# STM32H7XX_100PIN.net
KiCad netlist of a schematic drawn in Altium Designer
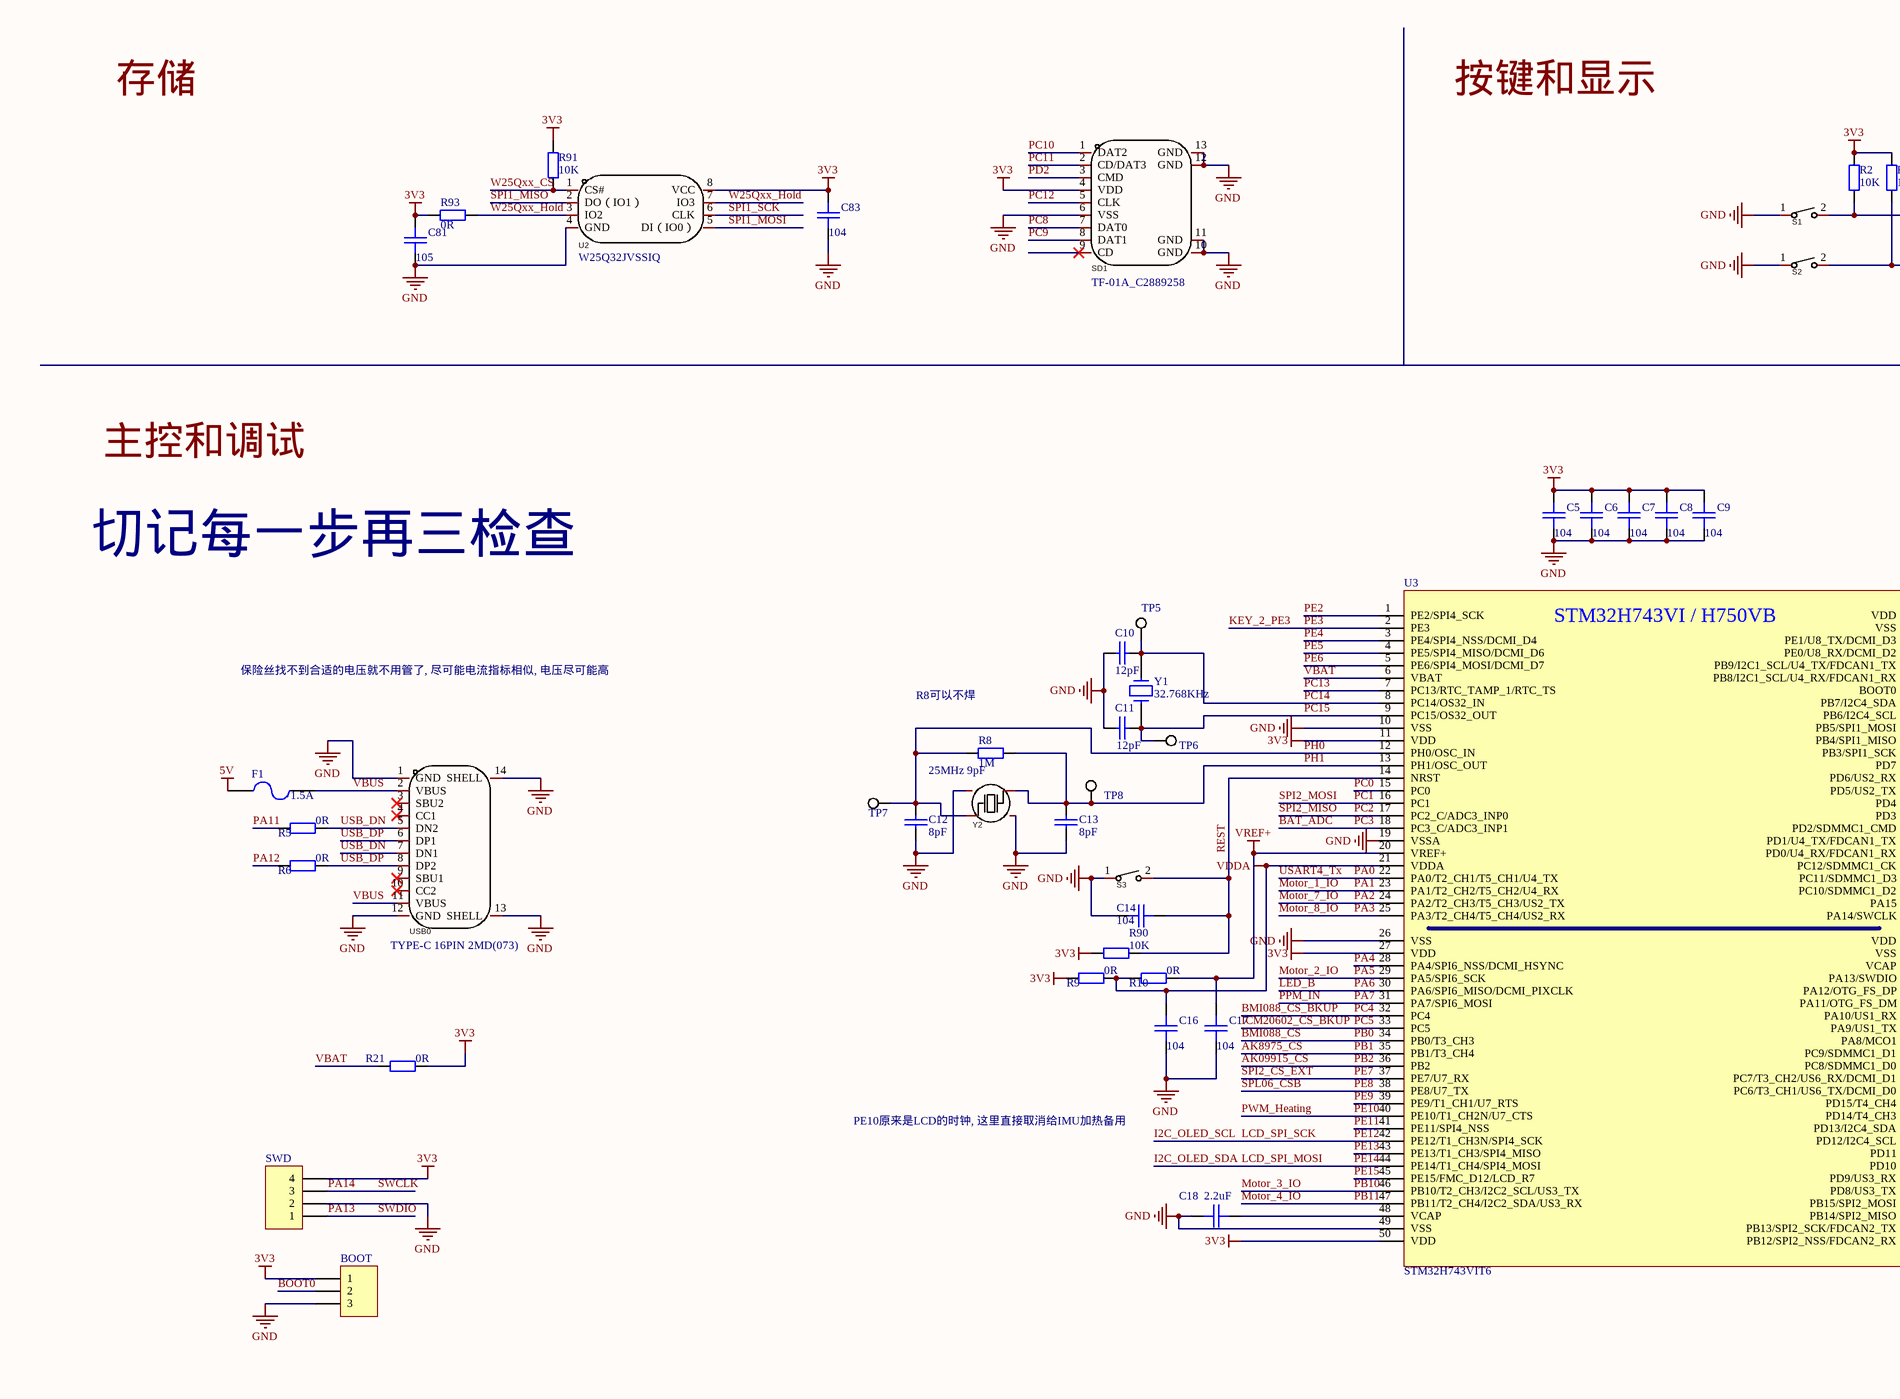
[diagram p0: STM32H7XX_100PIN.SchDoc, top left]
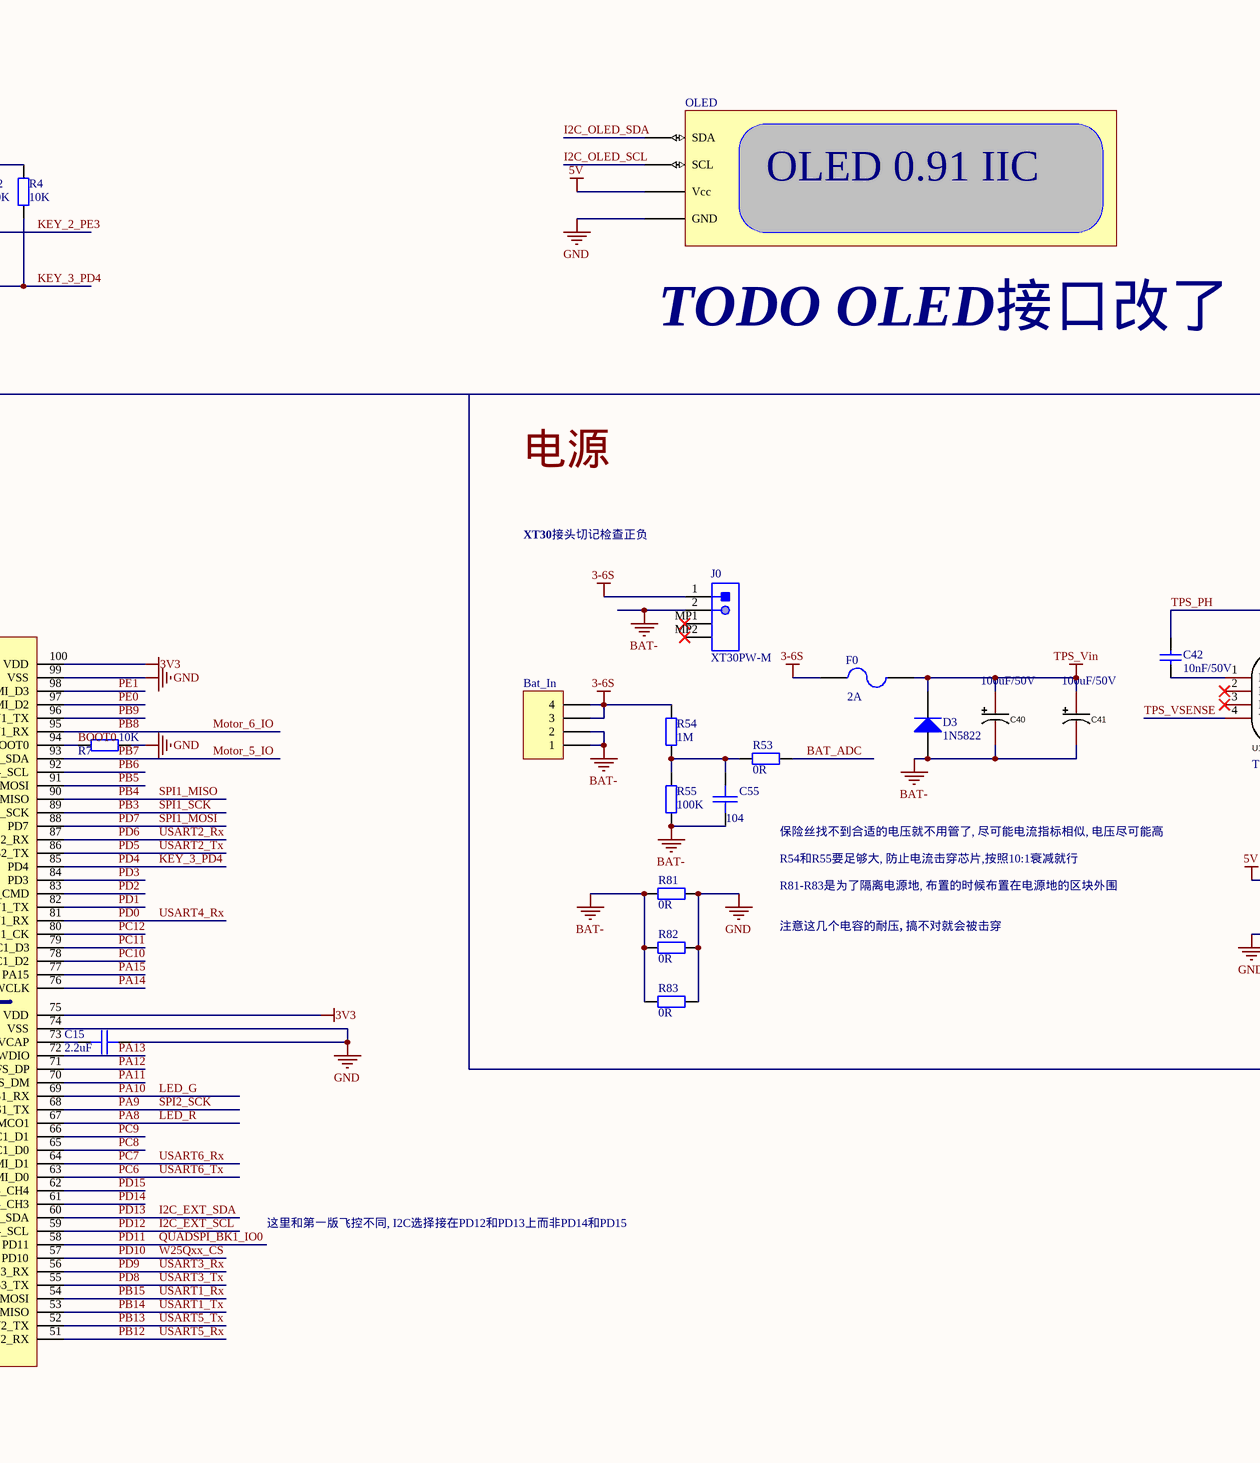
[diagram p1: STM32H7XX_100PIN.SchDoc, top middle]
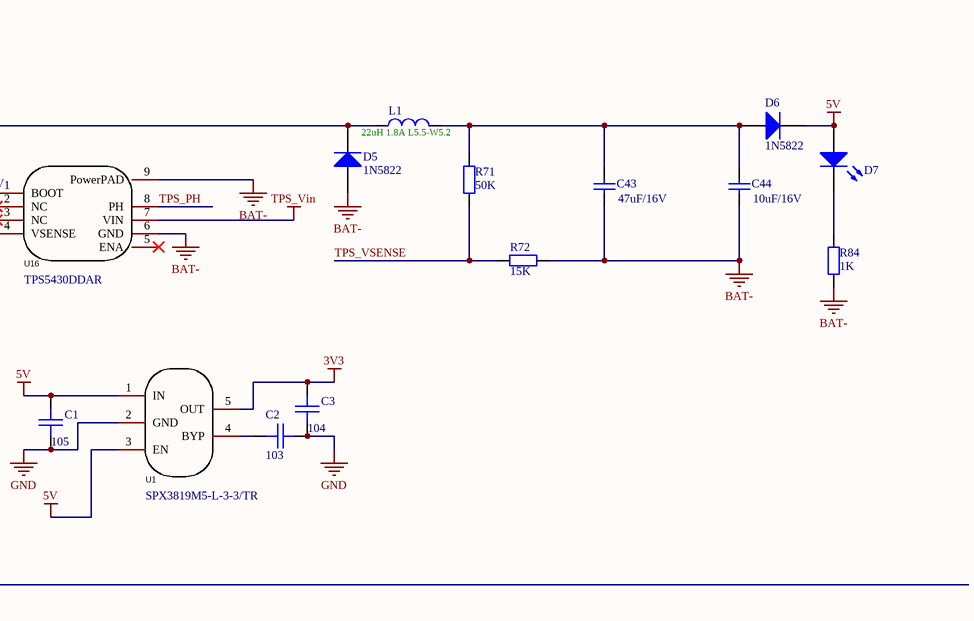
[diagram p2: STM32H7XX_100PIN.SchDoc, top right]
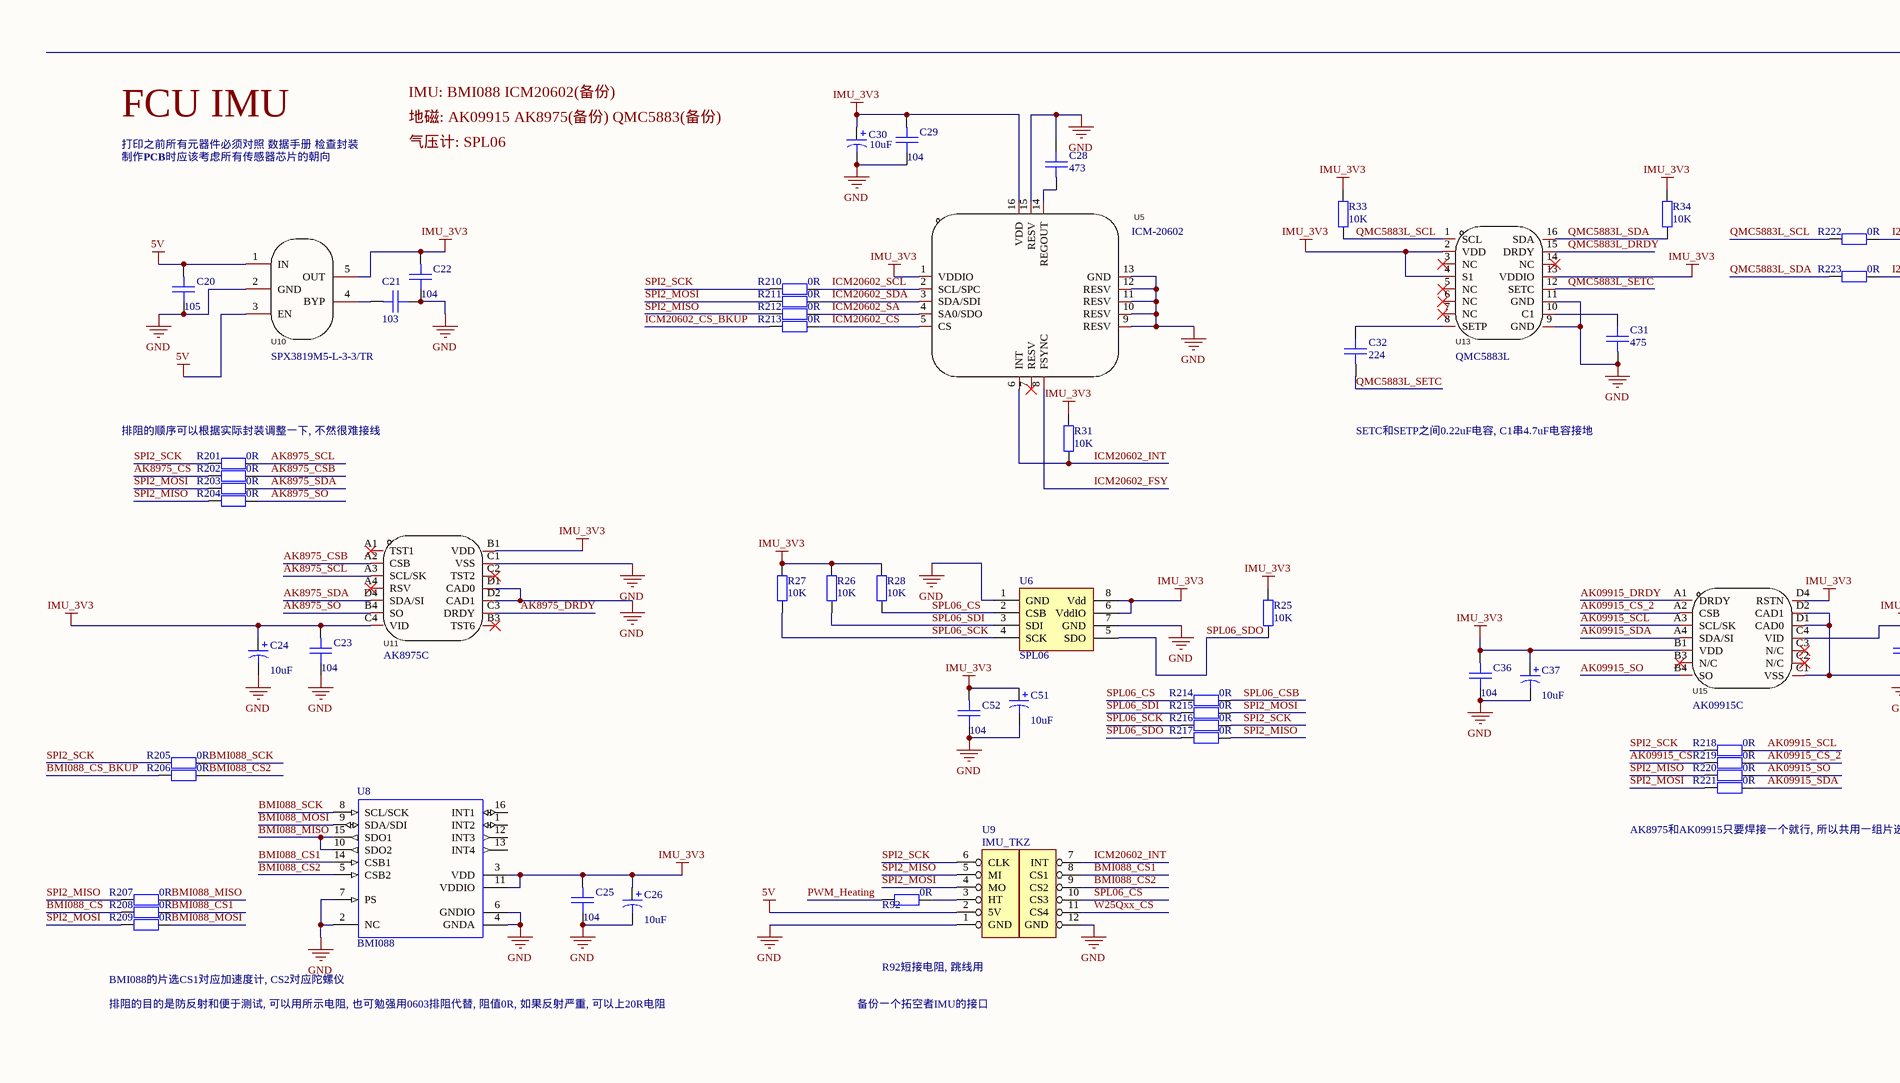
[diagram p3: STM32H7XX_100PIN.SchDoc, bottom left]
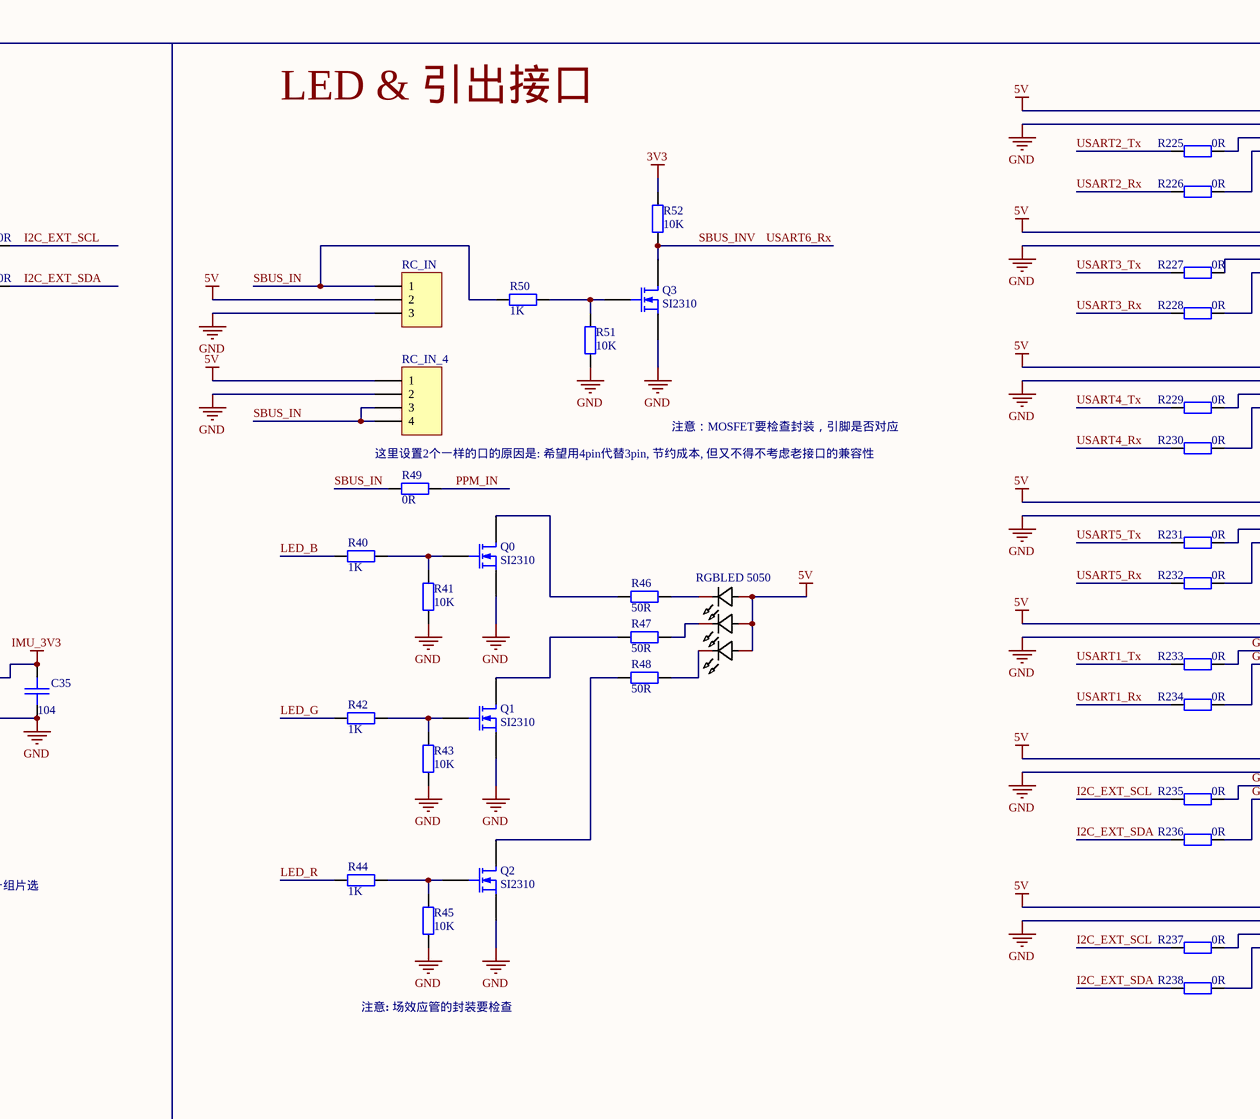
[diagram p4: STM32H7XX_100PIN.SchDoc, bottom middle]
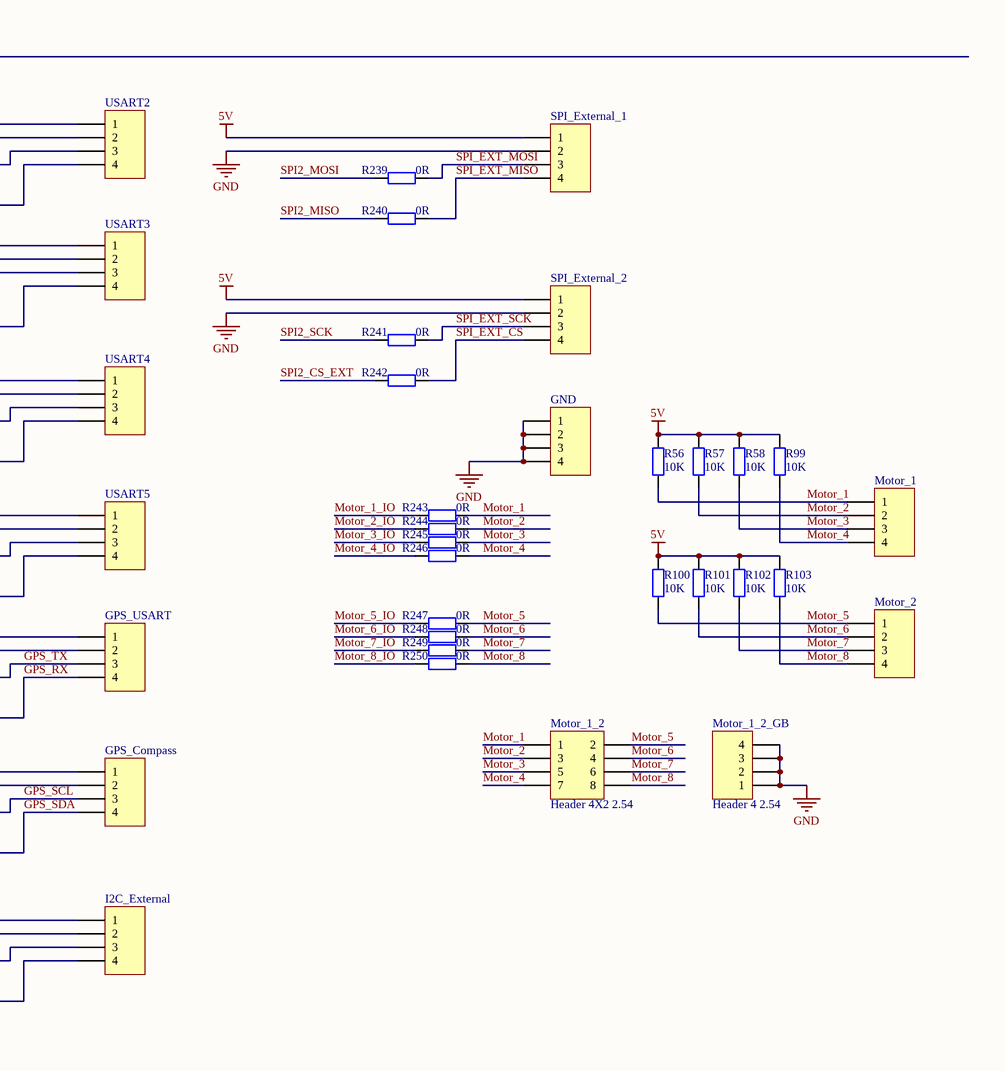
[diagram p5: STM32H7XX_100PIN.SchDoc, bottom right]

(export (version "E")
  (design (tool "Eeschema 10.0.6"))
  (components
    (comp (ref "Bat_In")
      (value "SH1.0-4")
      (footprint "飞控底板兼容版:SH_1.0_卧")
      (description "Header, 4-Pin")
      (fields (field (name "PUBLISHER") "Altium Limited"))
      (libsource (lib "") (part "Header 4_1"))
    )
    (comp (ref "BOOT")
      (value "Header 3 2.54")
      (footprint "HDR1X3")
      (description "Header, 3-Pin")
      (fields (field (name "PUBLISHER") "Altium Limited"))
      (libsource (lib "Miscellaneous Connectors") (part "Header 3"))
    )
    (comp (ref "C1") (value "105") (footprint "C0402") (libsource (lib "YT1_SCH_99SE") (part "CAP")))
    (comp (ref "C2") (value "103") (footprint "C0402") (libsource (lib "YT1_SCH_99SE") (part "CAP")))
    (comp (ref "C3") (value "104") (footprint "C0402") (libsource (lib "YT1_SCH_99SE") (part "CAP")))
    (comp (ref "C5") (value "104") (footprint "C0402") (libsource (lib "YT1_SCH_99SE") (part "CAP")))
    (comp (ref "C6") (value "104") (footprint "C0402") (libsource (lib "YT1_SCH_99SE") (part "CAP")))
    (comp (ref "C7") (value "104") (footprint "C0402") (libsource (lib "YT1_SCH_99SE") (part "CAP")))
    (comp (ref "C8") (value "104") (footprint "C0402") (libsource (lib "YT1_SCH_99SE") (part "CAP")))
    (comp (ref "C9") (value "104") (footprint "C0402") (libsource (lib "YT1_SCH_99SE") (part "CAP")))
    (comp (ref "C10")
      (value "12pF")
      (footprint "C0402")
      (description "Capcitor")
      (libsource (lib "LXKJSJ") (part "CAP"))
    )
    (comp (ref "C11")
      (value "12pF")
      (footprint "C0402")
      (description "Capcitor")
      (libsource (lib "LXKJSJ") (part "CAP"))
    )
    (comp (ref "C12")
      (value "8pF")
      (footprint "C0402")
      (description "Capcitor")
      (libsource (lib "LXKJSJ") (part "CAP"))
    )
    (comp (ref "C13")
      (value "8pF")
      (footprint "C0402")
      (description "Capcitor")
      (libsource (lib "LXKJSJ") (part "CAP"))
    )
    (comp (ref "C14") (value "104") (footprint "C0402") (libsource (lib "YT1_SCH_99SE") (part "CAP")))
    (comp (ref "C15") (value "2.2uF") (footprint "C0402") (libsource (lib "YT1_SCH_99SE") (part "CAP")))
    (comp (ref "C16") (value "104") (footprint "C0402") (libsource (lib "YT1_SCH_99SE") (part "CAP")))
    (comp (ref "C17") (value "104") (footprint "C0402") (libsource (lib "YT1_SCH_99SE") (part "CAP")))
    (comp (ref "C18") (value "2.2uF") (footprint "C0402") (libsource (lib "YT1_SCH_99SE") (part "CAP")))
    (comp (ref "C20") (value "105") (footprint "C0402") (libsource (lib "YT1_SCH_99SE") (part "CAP")))
    (comp (ref "C21") (value "103") (footprint "C0402") (libsource (lib "YT1_SCH_99SE") (part "CAP")))
    (comp (ref "C22") (value "104") (footprint "C0402") (libsource (lib "YT1_SCH_99SE") (part "CAP")))
    (comp (ref "C23") (value "104") (footprint "C0402") (libsource (lib "YT1_SCH_99SE") (part "CAP")))
    (comp (ref "C24")
      (value "10uF")
      (footprint "飞控-REV1:TAN-A(3216-18)")
      (description "Polarized Capacitor (Surface Mount)")
      (fields (field (name "PUBLISHER") "Altium Limited"))
      (libsource (lib "Miscellaneous Devices") (part "Cap Pol3"))
    )
    (comp (ref "C25") (value "104") (footprint "C0402") (libsource (lib "YT1_SCH_99SE") (part "CAP")))
    (comp (ref "C26")
      (value "10uF")
      (footprint "TAN-A(3216-18)")
      (description "Polarized Capacitor (Surface Mount)")
      (fields (field (name "PUBLISHER") "Altium Limited"))
      (libsource (lib "Miscellaneous Devices") (part "Cap Pol3"))
    )
    (comp (ref "C28") (value "473") (footprint "C0402") (libsource (lib "YT1_SCH_99SE") (part "CAP")))
    (comp (ref "C29") (value "104") (footprint "C0402") (libsource (lib "YT1_SCH_99SE") (part "CAP")))
    (comp (ref "C30")
      (value "10uF")
      (footprint "TAN-A(3216-18)")
      (description "Polarized Capacitor (Surface Mount)")
      (fields (field (name "PUBLISHER") "Altium Limited"))
      (libsource (lib "Miscellaneous Devices") (part "Cap Pol3"))
    )
    (comp (ref "C31") (value "475") (footprint "C0402") (libsource (lib "YT1_SCH_99SE") (part "CAP")))
    (comp (ref "C32") (value "224") (footprint "C0402") (libsource (lib "YT1_SCH_99SE") (part "CAP")))
    (comp (ref "C35") (value "104") (footprint "C0402") (libsource (lib "YT1_SCH_99SE") (part "CAP")))
    (comp (ref "C36") (value "104") (footprint "C0402") (libsource (lib "YT1_SCH_99SE") (part "CAP")))
    (comp (ref "C37")
      (value "10uF")
      (footprint "TAN-A(3216-18)")
      (description "Polarized Capacitor (Surface Mount)")
      (fields (field (name "PUBLISHER") "Altium Limited"))
      (libsource (lib "Miscellaneous Devices") (part "Cap Pol3"))
    )
    (comp (ref "C40")
      (value "100uF/50V")
      (footprint "CAP-SMD_BD6.3-L6.6-W6.6-FD")
      (fields
        (field (name "MANUFACTURER") "PANASONIC(����)")
        (field (name "MANUFACTURER PART") "EEEFTH101XAP")
        (field (name "TOLERANCE") "��20%")
      )
      (libsource (lib "FCU_Integrated_Library") (part "EEEFTH101XAP"))
    )
    (comp (ref "C41")
      (value "100uF/50V")
      (footprint "CAP-SMD_BD6.3-L6.6-W6.6-FD")
      (fields
        (field (name "MANUFACTURER") "PANASONIC(����)")
        (field (name "MANUFACTURER PART") "EEEFTH101XAP")
        (field (name "TOLERANCE") "��20%")
      )
      (libsource (lib "FCU_Integrated_Library") (part "EEEFTH101XAP"))
    )
    (comp (ref "C42")
      (value "10nF/50V")
      (footprint "STM32H_3D:C1206")
      (fields (field (name "TOLERANCE") "Â±10%"))
      (libsource (lib "FCU_Integrated_Library") (part "CMP-1035-02588-1"))
    )
    (comp (ref "C43")
      (value "47uF/16V")
      (footprint "STM32H_3D:C1210")
      (fields (field (name "TOLERANCE") "Â±10%"))
      (libsource (lib "FCU_Integrated_Library") (part "CMP-1035-02588-1"))
    )
    (comp (ref "C44")
      (value "10uF/16V")
      (footprint "STM32H_3D:C1210")
      (fields (field (name "TOLERANCE") "Â±10%"))
      (libsource (lib "FCU_Integrated_Library") (part "CMP-1035-02588-1"))
    )
    (comp (ref "C51")
      (value "10uF")
      (footprint "TAN-A(3216-18)")
      (description "Polarized Capacitor (Surface Mount)")
      (fields (field (name "PUBLISHER") "Altium Limited"))
      (libsource (lib "Miscellaneous Devices") (part "Cap Pol3"))
    )
    (comp (ref "C52") (value "104") (footprint "C0402") (libsource (lib "YT1_SCH_99SE") (part "CAP")))
    (comp (ref "C55") (value "104") (footprint "C0402") (libsource (lib "YT1_SCH_99SE") (part "CAP")))
    (comp (ref "C81") (value "105") (footprint "C0402") (libsource (lib "YT1_SCH_99SE") (part "CAP")))
    (comp (ref "C83") (value "104") (footprint "C0402") (libsource (lib "YT1_SCH_99SE") (part "CAP")))
    (comp (ref "D0")
      (value "RGBLED 5050")
      (footprint "LED-SMD_6P-L5.0-W5.0-TL_TC5050RGBF08")
      (fields
        (field (name "MANUFACTURER") "TCWIN(���)")
        (field (name "MANUFACTURER PART") "TC5050RGBF08-3CJH-AF53A")
      )
      (libsource (lib "FCU_Integrated_Library") (part "TC5050RGBF08-3CJH-AF53A"))
    )
    (comp (ref "D3")
      (value "1N5822")
      (footprint "FCU_Integrated_Library:SMA_L4.3-W2.5-LS5.0-RD")
      (description "SS34 Diode")
      (fields (field (name "PUBLISHER") "mazhongwei"))
      (libsource (lib "FCU_Integrated_Library") (part "SS34 Diode"))
    )
    (comp (ref "D5")
      (value "1N5822")
      (footprint "FCU_Integrated_Library:SMA_L4.3-W2.5-LS5.0-RD")
      (description "SS34 Diode")
      (fields (field (name "PUBLISHER") "mazhongwei"))
      (libsource (lib "FCU_Integrated_Library") (part "SS34 Diode"))
    )
    (comp (ref "D6")
      (value "1N5822")
      (footprint "FCU_Integrated_Library:SMA_L4.3-W2.5-LS5.0-RD")
      (description "SS34 Diode")
      (fields (field (name "PUBLISHER") "mazhongwei"))
      (libsource (lib "FCU_Integrated_Library") (part "SS34 Diode"))
    )
    (comp (ref "D7")
      (value "Red LED")
      (footprint "LED0603")
      (description "发光二极管")
      (fields (field (name "PUBLISHER") "Altium Limited"))
      (libsource (lib "主集成库") (part "LED0"))
    )
    (comp (ref "F0")
      (value "2A")
      (footprint "FU 1210")
      (description "保险丝")
      (fields (field (name "PUBLISHER") "Altium Limited"))
      (libsource (lib "fszhang") (part "Fuse 2"))
    )
    (comp (ref "F1")
      (value "1.5A")
      (footprint "FU 0402")
      (description "保险丝")
      (fields (field (name "PUBLISHER") "Altium Limited"))
      (libsource (lib "fszhang") (part "Fuse 2"))
    )
    (comp (ref "GND")
      (value "SH1.0-4")
      (footprint "飞控底板兼容版:SH_1.0_卧")
      (description "Header, 4-Pin")
      (fields (field (name "PUBLISHER") "Altium Limited"))
      (libsource (lib "Miscellaneous Connectors") (part "Header 4"))
    )
    (comp (ref "GPS_Compass")
      (value "SH1.0-4")
      (footprint "飞控底板兼容版:SH_1.0_卧")
      (description "Header, 4-Pin")
      (fields (field (name "PUBLISHER") "Altium Limited"))
      (libsource (lib "Miscellaneous Connectors") (part "Header 4"))
    )
    (comp (ref "GPS_USART")
      (value "SH1.0-4")
      (footprint "飞控底板兼容版:SH_1.0_卧")
      (description "Header, 4-Pin")
      (fields (field (name "PUBLISHER") "Altium Limited"))
      (libsource (lib "Miscellaneous Connectors") (part "Header 4"))
    )
    (comp (ref "I2C_External")
      (value "SH1.0-4")
      (footprint "飞控底板兼容版:SH_1.0_卧")
      (description "Header, 4-Pin")
      (fields (field (name "PUBLISHER") "Altium Limited"))
      (libsource (lib "Miscellaneous Connectors") (part "Header 4"))
    )
    (comp (ref "J0")
      (value "XT30PW-M")
      (footprint "AMASS-XT30PW-M")
      (description "XT Series Lithium Battery Male Connector, 4-pin TH")
      (fields (field (name "MANUFACTURER") "AMASS") (field (name "PUBLISHER") "Bolgen Studio"))
      (libsource (lib "Changzhou Amass Lithium Battery Connector") (part "XT30PW-M"))
    )
    (comp (ref "L1")
      (value "22uH 1.8A L5.5-W5.2")
      (footprint "FCU_Integrated_Library:IND-SMD_L5.5-W5.2")
      (libsource (lib "FCU_Integrated_Library") (part "INDUCTOR_2"))
    )
    (comp (ref "Motor_1")
      (value "SH1.0-4")
      (footprint "飞控底板兼容版:SH_1.0_卧")
      (description "Header, 4-Pin")
      (fields (field (name "PUBLISHER") "Altium Limited"))
      (libsource (lib "Miscellaneous Connectors") (part "Header 4"))
    )
    (comp (ref "Motor_1_2")
      (value "Header 4X2 2.54")
      (footprint "HDR2X4")
      (description "Header, 4-Pin, Dual row")
      (fields (field (name "PUBLISHER") "Altium Limited"))
      (libsource (lib "Miscellaneous Connectors") (part "Header 4X2"))
    )
    (comp (ref "Motor_1_2_GB")
      (value "Header 4 2.54")
      (footprint "Miscellaneous Connectors:HDR1X4")
      (description "Header, 4-Pin, Right Angle")
      (fields (field (name "PUBLISHER") "Altium Limited"))
      (libsource (lib "Miscellaneous Connectors") (part "Header 4H"))
    )
    (comp (ref "Motor_2")
      (value "SH1.0-4")
      (footprint "飞控底板兼容版:SH_1.0_卧")
      (description "Header, 4-Pin")
      (fields (field (name "PUBLISHER") "Altium Limited"))
      (libsource (lib "Miscellaneous Connectors") (part "Header 4"))
    )
    (comp (ref "OLED")
      (value "OLED 0.91")
      (footprint "PCBComponent_1")
      (libsource (lib "FCU_Integrated_Library") (part "OLED 0.91"))
    )
    (comp (ref "Q0")
      (value "SI2310")
      (footprint "Explorer STM32F407封装库:SOT-23R")
      (description "N-Channel MOSFET")
      (fields (field (name "PUBLISHER") "Altium Limited"))
      (libsource (lib "Miscellaneous Devices") (part "MOSFET-N"))
    )
    (comp (ref "Q1")
      (value "SI2310")
      (footprint "Explorer STM32F407封装库:SOT-23R")
      (description "N-Channel MOSFET")
      (fields (field (name "PUBLISHER") "Altium Limited"))
      (libsource (lib "Miscellaneous Devices") (part "MOSFET-N"))
    )
    (comp (ref "Q2")
      (value "SI2310")
      (footprint "Explorer STM32F407封装库:SOT-23R")
      (description "N-Channel MOSFET")
      (fields (field (name "PUBLISHER") "Altium Limited"))
      (libsource (lib "Miscellaneous Devices") (part "MOSFET-N"))
    )
    (comp (ref "Q3")
      (value "SI2310")
      (footprint "Explorer STM32F407封装库:SOT-23R")
      (description "N-Channel MOSFET")
      (fields (field (name "PUBLISHER") "Altium Limited"))
      (libsource (lib "Miscellaneous Devices") (part "MOSFET-N"))
    )
    (comp (ref "R2")
      (value "10K")
      (footprint "R0402")
      (description "贴片电阻")
      (fields (field (name "PUBLISHER") "Altium Limited"))
      (libsource (lib "") (part "Res1_1"))
    )
    (comp (ref "R4")
      (value "10K")
      (footprint "R0402")
      (description "贴片电阻")
      (fields (field (name "PUBLISHER") "Altium Limited"))
      (libsource (lib "") (part "Res1_1"))
    )
    (comp (ref "R5")
      (value "0R")
      (footprint "STM32H_3D:R0402")
      (description "贴片电阻")
      (fields (field (name "PUBLISHER") "Altium Limited"))
      (libsource (lib "主集成库") (part "Res1"))
    )
    (comp (ref "R6")
      (value "0R")
      (footprint "R0402")
      (description "贴片电阻")
      (fields (field (name "PUBLISHER") "Altium Limited"))
      (libsource (lib "主集成库") (part "Res1"))
    )
    (comp (ref "R7")
      (value "10K")
      (footprint "R0402")
      (description "贴片电阻")
      (fields (field (name "PUBLISHER") "Altium Limited"))
      (libsource (lib "主集成库") (part "Res1"))
    )
    (comp (ref "R8")
      (value "1M")
      (footprint "R0402")
      (description "贴片电阻")
      (fields (field (name "PUBLISHER") "Altium Limited"))
      (libsource (lib "") (part "Res1_3"))
    )
    (comp (ref "R9")
      (value "0R")
      (footprint "R0402")
      (description "贴片电阻")
      (fields (field (name "PUBLISHER") "Altium Limited"))
      (libsource (lib "主集成库") (part "Res1"))
    )
    (comp (ref "R10")
      (value "0R")
      (footprint "R0402")
      (description "贴片电阻")
      (fields (field (name "PUBLISHER") "Altium Limited"))
      (libsource (lib "主集成库") (part "Res1"))
    )
    (comp (ref "R21")
      (value "0R")
      (footprint "R0402")
      (description "贴片电阻")
      (fields (field (name "PUBLISHER") "Altium Limited"))
      (libsource (lib "主集成库") (part "Res1"))
    )
    (comp (ref "R25")
      (value "10K")
      (footprint "R0402")
      (description "贴片电阻")
      (fields (field (name "PUBLISHER") "Altium Limited"))
      (libsource (lib "") (part "Res1_1"))
    )
    (comp (ref "R26")
      (value "10K")
      (footprint "R0402")
      (description "贴片电阻")
      (fields (field (name "PUBLISHER") "Altium Limited"))
      (libsource (lib "") (part "Res1_1"))
    )
    (comp (ref "R27")
      (value "10K")
      (footprint "R0402")
      (description "贴片电阻")
      (fields (field (name "PUBLISHER") "Altium Limited"))
      (libsource (lib "") (part "Res1_1"))
    )
    (comp (ref "R28")
      (value "10K")
      (footprint "R0402")
      (description "贴片电阻")
      (fields (field (name "PUBLISHER") "Altium Limited"))
      (libsource (lib "") (part "Res1_1"))
    )
    (comp (ref "R31")
      (value "10K")
      (footprint "R0402")
      (description "贴片电阻")
      (fields (field (name "PUBLISHER") "Altium Limited"))
      (libsource (lib "") (part "Res1_1"))
    )
    (comp (ref "R33")
      (value "10K")
      (footprint "R0402")
      (description "贴片电阻")
      (fields (field (name "PUBLISHER") "Altium Limited"))
      (libsource (lib "") (part "Res1_1"))
    )
    (comp (ref "R34")
      (value "10K")
      (footprint "R0402")
      (description "贴片电阻")
      (fields (field (name "PUBLISHER") "Altium Limited"))
      (libsource (lib "") (part "Res1_1"))
    )
    (comp (ref "R40")
      (value "1K")
      (footprint "R0402")
      (description "贴片电阻")
      (fields (field (name "PUBLISHER") "Altium Limited"))
      (libsource (lib "") (part "Res1_2"))
    )
    (comp (ref "R41")
      (value "10K")
      (footprint "R0402")
      (description "贴片电阻")
      (fields (field (name "PUBLISHER") "Altium Limited"))
      (libsource (lib "fszhang") (part "Res1"))
    )
    (comp (ref "R42")
      (value "1K")
      (footprint "R0402")
      (description "贴片电阻")
      (fields (field (name "PUBLISHER") "Altium Limited"))
      (libsource (lib "") (part "Res1_2"))
    )
    (comp (ref "R43")
      (value "10K")
      (footprint "R0402")
      (description "贴片电阻")
      (fields (field (name "PUBLISHER") "Altium Limited"))
      (libsource (lib "fszhang") (part "Res1"))
    )
    (comp (ref "R44")
      (value "1K")
      (footprint "R0402")
      (description "贴片电阻")
      (fields (field (name "PUBLISHER") "Altium Limited"))
      (libsource (lib "") (part "Res1_2"))
    )
    (comp (ref "R45")
      (value "10K")
      (footprint "R0402")
      (description "贴片电阻")
      (fields (field (name "PUBLISHER") "Altium Limited"))
      (libsource (lib "fszhang") (part "Res1"))
    )
    (comp (ref "R46")
      (value "50R")
      (footprint "R0402")
      (description "贴片电阻")
      (fields (field (name "PUBLISHER") "Altium Limited"))
      (libsource (lib "") (part "10K_1"))
    )
    (comp (ref "R47")
      (value "50R")
      (footprint "R0402")
      (description "贴片电阻")
      (fields (field (name "PUBLISHER") "Altium Limited"))
      (libsource (lib "") (part "10K_1"))
    )
    (comp (ref "R48")
      (value "50R")
      (footprint "R0402")
      (description "贴片电阻")
      (fields (field (name "PUBLISHER") "Altium Limited"))
      (libsource (lib "") (part "10K_1"))
    )
    (comp (ref "R49")
      (value "0R")
      (footprint "R0402")
      (description "贴片电阻")
      (fields (field (name "PUBLISHER") "Altium Limited"))
      (libsource (lib "") (part "Res1_2"))
    )
    (comp (ref "R50")
      (value "1K")
      (footprint "R0402")
      (description "贴片电阻")
      (fields (field (name "PUBLISHER") "Altium Limited"))
      (libsource (lib "") (part "Res1_2"))
    )
    (comp (ref "R51")
      (value "10K")
      (footprint "R0402")
      (description "贴片电阻")
      (fields (field (name "PUBLISHER") "Altium Limited"))
      (libsource (lib "fszhang") (part "Res1"))
    )
    (comp (ref "R52")
      (value "10K")
      (footprint "R0402")
      (description "贴片电阻")
      (fields (field (name "PUBLISHER") "Altium Limited"))
      (libsource (lib "fszhang") (part "Res1"))
    )
    (comp (ref "R53")
      (value "0R")
      (footprint "R0402")
      (description "贴片电阻")
      (fields (field (name "PUBLISHER") "Altium Limited"))
      (libsource (lib "") (part "Res1_2"))
    )
    (comp (ref "R54")
      (value "1M")
      (footprint "R0402")
      (description "贴片电阻")
      (fields (field (name "PUBLISHER") "Altium Limited"))
      (libsource (lib "fszhang") (part "Res1"))
    )
    (comp (ref "R55")
      (value "100K")
      (footprint "R0402")
      (description "贴片电阻")
      (fields (field (name "PUBLISHER") "Altium Limited"))
      (libsource (lib "fszhang") (part "Res1"))
    )
    (comp (ref "R56")
      (value "10K")
      (footprint "R0402")
      (description "贴片电阻")
      (fields (field (name "PUBLISHER") "Altium Limited"))
      (libsource (lib "fszhang") (part "10K"))
    )
    (comp (ref "R57")
      (value "10K")
      (footprint "R0402")
      (description "贴片电阻")
      (fields (field (name "PUBLISHER") "Altium Limited"))
      (libsource (lib "fszhang") (part "10K"))
    )
    (comp (ref "R58")
      (value "10K")
      (footprint "R0402")
      (description "贴片电阻")
      (fields (field (name "PUBLISHER") "Altium Limited"))
      (libsource (lib "fszhang") (part "10K"))
    )
    (comp (ref "R71")
      (value "50K")
      (footprint "0805")
      (description "贴片电阻")
      (fields (field (name "PUBLISHER") "Altium Limited"))
      (libsource (lib "fszhang") (part "Res1"))
    )
    (comp (ref "R72")
      (value "15K")
      (footprint "0805")
      (description "贴片电阻")
      (fields (field (name "PUBLISHER") "Altium Limited"))
      (libsource (lib "") (part "Res1_3"))
    )
    (comp (ref "R81")
      (value "0R")
      (footprint "R0402")
      (description "贴片电阻")
      (fields (field (name "PUBLISHER") "Altium Limited"))
      (libsource (lib "") (part "Res1_2"))
    )
    (comp (ref "R82")
      (value "0R")
      (footprint "R0402")
      (description "贴片电阻")
      (fields (field (name "PUBLISHER") "Altium Limited"))
      (libsource (lib "") (part "Res1_2"))
    )
    (comp (ref "R83")
      (value "0R")
      (footprint "R0402")
      (description "贴片电阻")
      (fields (field (name "PUBLISHER") "Altium Limited"))
      (libsource (lib "") (part "Res1_2"))
    )
    (comp (ref "R84")
      (value "1K")
      (footprint "R0402")
      (description "贴片电阻")
      (fields (field (name "PUBLISHER") "Altium Limited"))
      (libsource (lib "fszhang") (part "Res1"))
    )
    (comp (ref "R90")
      (value "10K")
      (footprint "R0402")
      (description "贴片电阻")
      (fields (field (name "PUBLISHER") "Altium Limited"))
      (libsource (lib "主集成库") (part "Res1"))
    )
    (comp (ref "R91")
      (value "10K")
      (footprint "R0402")
      (description "贴片电阻")
      (fields (field (name "PUBLISHER") "Altium Limited"))
      (libsource (lib "") (part "Res1_1"))
    )
    (comp (ref "R92")
      (value "0R")
      (footprint "R0402")
      (description "贴片电阻")
      (fields (field (name "PUBLISHER") "Altium Limited"))
      (libsource (lib "主集成库") (part "Res1"))
    )
    (comp (ref "R93")
      (value "0R")
      (footprint "R0402")
      (description "贴片电阻")
      (fields (field (name "Comment") "10K") (field (name "PUBLISHER") "Altium Limited"))
      (libsource (lib "") (part "Res1_2"))
    )
    (comp (ref "R99")
      (value "10K")
      (footprint "R0402")
      (description "贴片电阻")
      (fields (field (name "PUBLISHER") "Altium Limited"))
      (libsource (lib "fszhang") (part "10K"))
    )
    (comp (ref "R100")
      (value "10K")
      (footprint "R0402")
      (description "贴片电阻")
      (fields (field (name "PUBLISHER") "Altium Limited"))
      (libsource (lib "fszhang") (part "10K"))
    )
    (comp (ref "R101")
      (value "10K")
      (footprint "R0402")
      (description "贴片电阻")
      (fields (field (name "PUBLISHER") "Altium Limited"))
      (libsource (lib "fszhang") (part "10K"))
    )
    (comp (ref "R102")
      (value "10K")
      (footprint "R0402")
      (description "贴片电阻")
      (fields (field (name "PUBLISHER") "Altium Limited"))
      (libsource (lib "fszhang") (part "10K"))
    )
    (comp (ref "R103")
      (value "10K")
      (footprint "R0402")
      (description "贴片电阻")
      (fields (field (name "PUBLISHER") "Altium Limited"))
      (libsource (lib "fszhang") (part "10K"))
    )
    (comp (ref "R201")
      (value "0R")
      (footprint "R0402")
      (description "贴片电阻")
      (fields (field (name "PUBLISHER") "Altium Limited"))
      (libsource (lib "主集成库") (part "Res1"))
    )
    (comp (ref "R202")
      (value "0R")
      (footprint "R0402")
      (description "贴片电阻")
      (fields (field (name "PUBLISHER") "Altium Limited"))
      (libsource (lib "主集成库") (part "Res1"))
    )
    (comp (ref "R203")
      (value "0R")
      (footprint "R0402")
      (description "贴片电阻")
      (fields (field (name "PUBLISHER") "Altium Limited"))
      (libsource (lib "主集成库") (part "Res1"))
    )
    (comp (ref "R204")
      (value "0R")
      (footprint "R0402")
      (description "贴片电阻")
      (fields (field (name "PUBLISHER") "Altium Limited"))
      (libsource (lib "主集成库") (part "Res1"))
    )
    (comp (ref "R205")
      (value "0R")
      (footprint "R0402")
      (description "贴片电阻")
      (fields (field (name "PUBLISHER") "Altium Limited"))
      (libsource (lib "主集成库") (part "Res1"))
    )
    (comp (ref "R206")
      (value "0R")
      (footprint "R0402")
      (description "贴片电阻")
      (fields (field (name "PUBLISHER") "Altium Limited"))
      (libsource (lib "主集成库") (part "Res1"))
    )
    (comp (ref "R207")
      (value "0R")
      (footprint "R0402")
      (description "贴片电阻")
      (fields (field (name "PUBLISHER") "Altium Limited"))
      (libsource (lib "主集成库") (part "Res1"))
    )
    (comp (ref "R208")
      (value "0R")
      (footprint "R0402")
      (description "贴片电阻")
      (fields (field (name "PUBLISHER") "Altium Limited"))
      (libsource (lib "主集成库") (part "Res1"))
    )
    (comp (ref "R209")
      (value "0R")
      (footprint "R0402")
      (description "贴片电阻")
      (fields (field (name "PUBLISHER") "Altium Limited"))
      (libsource (lib "主集成库") (part "Res1"))
    )
    (comp (ref "R210")
      (value "0R")
      (footprint "R0402")
      (description "贴片电阻")
      (fields (field (name "PUBLISHER") "Altium Limited"))
      (libsource (lib "主集成库") (part "Res1"))
    )
    (comp (ref "R211")
      (value "0R")
      (footprint "R0402")
      (description "贴片电阻")
      (fields (field (name "PUBLISHER") "Altium Limited"))
      (libsource (lib "主集成库") (part "Res1"))
    )
    (comp (ref "R212")
      (value "0R")
      (footprint "R0402")
      (description "贴片电阻")
      (fields (field (name "PUBLISHER") "Altium Limited"))
      (libsource (lib "主集成库") (part "Res1"))
    )
    (comp (ref "R213")
      (value "0R")
      (footprint "R0402")
      (description "贴片电阻")
      (fields (field (name "PUBLISHER") "Altium Limited"))
      (libsource (lib "主集成库") (part "Res1"))
    )
    (comp (ref "R214")
      (value "0R")
      (footprint "R0402")
      (description "贴片电阻")
      (fields (field (name "PUBLISHER") "Altium Limited"))
      (libsource (lib "主集成库") (part "Res1"))
    )
    (comp (ref "R215")
      (value "0R")
      (footprint "R0402")
      (description "贴片电阻")
      (fields (field (name "PUBLISHER") "Altium Limited"))
      (libsource (lib "主集成库") (part "Res1"))
    )
    (comp (ref "R216")
      (value "0R")
      (footprint "R0402")
      (description "贴片电阻")
      (fields (field (name "PUBLISHER") "Altium Limited"))
      (libsource (lib "主集成库") (part "Res1"))
    )
    (comp (ref "R217")
      (value "0R")
      (footprint "R0402")
      (description "贴片电阻")
      (fields (field (name "PUBLISHER") "Altium Limited"))
      (libsource (lib "主集成库") (part "Res1"))
    )
    (comp (ref "R218")
      (value "0R")
      (footprint "R0402")
      (description "贴片电阻")
      (fields (field (name "PUBLISHER") "Altium Limited"))
      (libsource (lib "主集成库") (part "Res1"))
    )
    (comp (ref "R219")
      (value "0R")
      (footprint "R0402")
      (description "贴片电阻")
      (fields (field (name "PUBLISHER") "Altium Limited"))
      (libsource (lib "主集成库") (part "Res1"))
    )
    (comp (ref "R220")
      (value "0R")
      (footprint "R0402")
      (description "贴片电阻")
      (fields (field (name "PUBLISHER") "Altium Limited"))
      (libsource (lib "主集成库") (part "Res1"))
    )
    (comp (ref "R221")
      (value "0R")
      (footprint "R0402")
      (description "贴片电阻")
      (fields (field (name "PUBLISHER") "Altium Limited"))
      (libsource (lib "主集成库") (part "Res1"))
    )
    (comp (ref "R222")
      (value "0R")
      (footprint "R0402")
      (description "贴片电阻")
      (fields (field (name "PUBLISHER") "Altium Limited"))
      (libsource (lib "主集成库") (part "Res1"))
    )
    (comp (ref "R223")
      (value "0R")
      (footprint "R0402")
      (description "贴片电阻")
      (fields (field (name "PUBLISHER") "Altium Limited"))
      (libsource (lib "主集成库") (part "Res1"))
    )
    (comp (ref "R225")
      (value "0R")
      (footprint "R0402")
      (description "贴片电阻")
      (fields (field (name "PUBLISHER") "Altium Limited"))
      (libsource (lib "主集成库") (part "Res1"))
    )
    (comp (ref "R226")
      (value "0R")
      (footprint "R0402")
      (description "贴片电阻")
      (fields (field (name "PUBLISHER") "Altium Limited"))
      (libsource (lib "主集成库") (part "Res1"))
    )
    (comp (ref "R227")
      (value "0R")
      (footprint "R0402")
      (description "贴片电阻")
      (fields (field (name "PUBLISHER") "Altium Limited"))
      (libsource (lib "主集成库") (part "Res1"))
    )
    (comp (ref "R228")
      (value "0R")
      (footprint "R0402")
      (description "贴片电阻")
      (fields (field (name "PUBLISHER") "Altium Limited"))
      (libsource (lib "主集成库") (part "Res1"))
    )
    (comp (ref "R229")
      (value "0R")
      (footprint "R0402")
      (description "贴片电阻")
      (fields (field (name "PUBLISHER") "Altium Limited"))
      (libsource (lib "主集成库") (part "Res1"))
    )
    (comp (ref "R230")
      (value "0R")
      (footprint "R0402")
      (description "贴片电阻")
      (fields (field (name "PUBLISHER") "Altium Limited"))
      (libsource (lib "主集成库") (part "Res1"))
    )
    (comp (ref "R231")
      (value "0R")
      (footprint "R0402")
      (description "贴片电阻")
      (fields (field (name "PUBLISHER") "Altium Limited"))
      (libsource (lib "主集成库") (part "Res1"))
    )
    (comp (ref "R232")
      (value "0R")
      (footprint "R0402")
      (description "贴片电阻")
      (fields (field (name "PUBLISHER") "Altium Limited"))
      (libsource (lib "主集成库") (part "Res1"))
    )
    (comp (ref "R233")
      (value "0R")
      (footprint "R0402")
      (description "贴片电阻")
      (fields (field (name "PUBLISHER") "Altium Limited"))
      (libsource (lib "主集成库") (part "Res1"))
    )
    (comp (ref "R234")
      (value "0R")
      (footprint "R0402")
      (description "贴片电阻")
      (fields (field (name "PUBLISHER") "Altium Limited"))
      (libsource (lib "主集成库") (part "Res1"))
    )
    (comp (ref "R235")
      (value "0R")
      (footprint "R0402")
      (description "贴片电阻")
      (fields (field (name "PUBLISHER") "Altium Limited"))
      (libsource (lib "主集成库") (part "Res1"))
    )
    (comp (ref "R236")
      (value "0R")
      (footprint "R0402")
      (description "贴片电阻")
      (fields (field (name "PUBLISHER") "Altium Limited"))
      (libsource (lib "主集成库") (part "Res1"))
    )
    (comp (ref "R237")
      (value "0R")
      (footprint "R0402")
      (description "贴片电阻")
      (fields (field (name "PUBLISHER") "Altium Limited"))
      (libsource (lib "主集成库") (part "Res1"))
    )
    (comp (ref "R238")
      (value "0R")
      (footprint "R0402")
      (description "贴片电阻")
      (fields (field (name "PUBLISHER") "Altium Limited"))
      (libsource (lib "主集成库") (part "Res1"))
    )
    (comp (ref "R239")
      (value "0R")
      (footprint "R0402")
      (description "贴片电阻")
      (fields (field (name "PUBLISHER") "Altium Limited"))
      (libsource (lib "主集成库") (part "Res1"))
    )
    (comp (ref "R240")
      (value "0R")
      (footprint "R0402")
      (description "贴片电阻")
      (fields (field (name "PUBLISHER") "Altium Limited"))
      (libsource (lib "主集成库") (part "Res1"))
    )
    (comp (ref "R241")
      (value "0R")
      (footprint "R0402")
      (description "贴片电阻")
      (fields (field (name "PUBLISHER") "Altium Limited"))
      (libsource (lib "主集成库") (part "Res1"))
    )
    (comp (ref "R242")
      (value "0R")
      (footprint "R0402")
      (description "贴片电阻")
      (fields (field (name "PUBLISHER") "Altium Limited"))
      (libsource (lib "主集成库") (part "Res1"))
    )
    (comp (ref "R243")
      (value "0R")
      (footprint "R0402")
      (description "贴片电阻")
      (fields (field (name "PUBLISHER") "Altium Limited"))
      (libsource (lib "主集成库") (part "Res1"))
    )
    (comp (ref "R244")
      (value "0R")
      (footprint "R0402")
      (description "贴片电阻")
      (fields (field (name "PUBLISHER") "Altium Limited"))
      (libsource (lib "主集成库") (part "Res1"))
    )
    (comp (ref "R245")
      (value "0R")
      (footprint "R0402")
      (description "贴片电阻")
      (fields (field (name "PUBLISHER") "Altium Limited"))
      (libsource (lib "主集成库") (part "Res1"))
    )
    (comp (ref "R246")
      (value "0R")
      (footprint "R0402")
      (description "贴片电阻")
      (fields (field (name "PUBLISHER") "Altium Limited"))
      (libsource (lib "主集成库") (part "Res1"))
    )
    (comp (ref "R247")
      (value "0R")
      (footprint "R0402")
      (description "贴片电阻")
      (fields (field (name "PUBLISHER") "Altium Limited"))
      (libsource (lib "主集成库") (part "Res1"))
    )
    (comp (ref "R248")
      (value "0R")
      (footprint "R0402")
      (description "贴片电阻")
      (fields (field (name "PUBLISHER") "Altium Limited"))
      (libsource (lib "主集成库") (part "Res1"))
    )
    (comp (ref "R249")
      (value "0R")
      (footprint "R0402")
      (description "贴片电阻")
      (fields (field (name "PUBLISHER") "Altium Limited"))
      (libsource (lib "主集成库") (part "Res1"))
    )
    (comp (ref "R250")
      (value "0R")
      (footprint "R0402")
      (description "贴片电阻")
      (fields (field (name "PUBLISHER") "Altium Limited"))
      (libsource (lib "主集成库") (part "Res1"))
    )
    (comp (ref "RC_IN")
      (value "SH 1.0-3")
      (footprint "飞控底板兼容版:SH_1.0_3P卧")
      (description "Header, 3-Pin")
      (fields (field (name "PUBLISHER") "Altium Limited"))
      (libsource (lib "Miscellaneous Connectors") (part "Header 3"))
    )
    (comp (ref "RC_IN_4")
      (value "SH1.0-4")
      (footprint "飞控底板兼容版:SH_1.0_卧")
      (description "Header, 4-Pin")
      (fields (field (name "PUBLISHER") "Altium Limited"))
      (libsource (lib "Miscellaneous Connectors") (part "Header 4"))
    )
    (comp (ref "S1")
      (value "TS-1092S-B3D2-G")
      (footprint "SW-SMD_L6.1-W3.6-LS7.9")
      (fields (field (name "MANUFACTURER") "Yuandi(Ԫ��)"))
      (libsource (lib "FCU_Integrated_Library") (part "TS-1092S-B3D2-G"))
    )
    (comp (ref "S2")
      (value "TS-1092S-B3D2-G")
      (footprint "SW-SMD_L6.1-W3.6-LS7.9")
      (fields (field (name "MANUFACTURER") "Yuandi(Ԫ��)"))
      (libsource (lib "FCU_Integrated_Library") (part "TS-1092S-B3D2-G"))
    )
    (comp (ref "S3")
      (value "TS-1092S-B3D2-G")
      (footprint "SW-SMD_L6.1-W3.6-LS7.9")
      (fields (field (name "MANUFACTURER") "Yuandi(Ԫ��)"))
      (libsource (lib "FCU_Integrated_Library") (part "TS-1092S-B3D2-G"))
    )
    (comp (ref "SD1")
      (value "TF-01A_C2889258")
      (footprint "TF-SMD_TF-02")
      (fields (field (name "MANUFACTURER") "Yuandi(Ԫ��)") (field (name "MANUFACTURER PART") "TF-01A"))
      (libsource (lib "FCU_Integrated_Library") (part "TF-01A_C2889258"))
    )
    (comp (ref "SPI_External_1")
      (value "SH1.0-4")
      (footprint "飞控底板兼容版:SH_1.0_卧")
      (description "Header, 4-Pin")
      (fields (field (name "PUBLISHER") "Altium Limited"))
      (libsource (lib "Miscellaneous Connectors") (part "Header 4"))
    )
    (comp (ref "SPI_External_2")
      (value "SH1.0-4")
      (footprint "飞控底板兼容版:SH_1.0_卧")
      (description "Header, 4-Pin")
      (fields (field (name "PUBLISHER") "Altium Limited"))
      (libsource (lib "Miscellaneous Connectors") (part "Header 4"))
    )
    (comp (ref "SWD")
      (value "SH1.0-4")
      (footprint "飞控底板兼容版:SH_1.0_卧")
      (description "Header, 4-Pin")
      (fields (field (name "PUBLISHER") "Altium Limited"))
      (libsource (lib "") (part "Header 4_1"))
    )
    (comp (ref "TP5")
      (value "Test Point")
      (footprint "TP-SM-C-100")
      (libsource (lib "NRI Maker Library") (part "TESTPOINT_WHITE"))
    )
    (comp (ref "TP6")
      (value "Test Point")
      (footprint "TP-SM-C-100")
      (libsource (lib "NRI Maker Library") (part "TESTPOINT_WHITE"))
    )
    (comp (ref "TP7")
      (value "Test Point")
      (footprint "TP-SM-C-100")
      (libsource (lib "NRI Maker Library") (part "TESTPOINT_WHITE"))
    )
    (comp (ref "TP8")
      (value "Test Point")
      (footprint "TP-SM-C-100")
      (libsource (lib "NRI Maker Library") (part "TESTPOINT_WHITE"))
    )
    (comp (ref "U1")
      (value "SPX3819M5-L-3-3/TR")
      (footprint "SOT-23-5_L3.0-W1.7-P0.95-LS2.8-BL")
      (fields (field (name "MANUFACTURER") "MaxLinear(����)"))
      (libsource (lib "FCU_Integrated_Library") (part "SPX3819M5-L-3-3/TR"))
    )
    (comp (ref "U2")
      (value "W25Q32JVSSIQ")
      (footprint "SOIC-8_L5.3-W5.3-P1.27-LS8.0-BL")
      (fields (field (name "MANUFACTURER") "WINBOND(����)"))
      (libsource (lib "FCU_Integrated_Library") (part "W25Q32JVSSIQ_C82344"))
    )
    (comp (ref "U3")
      (value "STM32H743VIT6")
      (footprint "LQFP100-14*14")
      (libsource (lib "STM32_F4VX_M") (part "STM32H7XX_100PIN"))
    )
    (comp (ref "U5")
      (value "ICM-20602")
      (footprint "LGA-16_L3.0-W3.0-P0.50-BL")
      (fields (field (name "MANUFACTURER") "TDK InvenSense(Ӧ��ʢ)"))
      (libsource (lib "FCU_Integrated_Library") (part "ICM-20602"))
    )
    (comp (ref "U6")
      (value "SPL06")
      (footprint "LGA-2_5X2MM")
      (description "FBM320\\BMP280\\SPL06")
      (fields (field (name "PUBLISHER") "mazhongwei"))
      (libsource (lib "RoboFly") (part "FBM320"))
    )
    (comp (ref "U8")
      (value "BMI088")
      (footprint "BOSC-LGA-16-BMI088_V")
      (description "6-axis Motion Tracking for High-performance Applications,")
      (libsource (lib "FCU_Integrated_Library") (part "BOSC-BMI088-LGA-16"))
    )
    (comp (ref "U9")
      (value "IMU_TKZ")
      (footprint "IMU_TKZ_SM2")
      (libsource (lib "FCU_Integrated_Library") (part "IMU_TKZ"))
    )
    (comp (ref "U10")
      (value "SPX3819M5-L-3-3/TR")
      (footprint "SOT-23-5_L3.0-W1.7-P0.95-LS2.8-BL")
      (fields (field (name "MANUFACTURER") "MaxLinear(����)"))
      (libsource (lib "FCU_Integrated_Library") (part "SPX3819M5-L-3-3/TR"))
    )
    (comp (ref "U11")
      (value "AK8975C")
      (footprint "BGA-14_L2.0-W2.0-P0.50-BR_AK8975")
      (fields (field (name "MANUFACTURER") "AKM"))
      (libsource (lib "FCU_Integrated_Library") (part "AK8975C"))
    )
    (comp (ref "U13")
      (value "QMC5883L")
      (footprint "LGA-16_L3.0-W3.0-P0.50-BL_SQ")
      (fields (field (name "MANUFACTURER") "QST(�Ϻ����)"))
      (libsource (lib "FCU_Integrated_Library") (part "QMC5883L"))
    )
    (comp (ref "U15")
      (value "AK09915C")
      (footprint "BGA-14_L1.6-W1.6-BR-AK09915C")
      (fields (field (name "MANUFACTURER") "AKM"))
      (libsource (lib "FCU_Integrated_Library") (part "AK09915C"))
    )
    (comp (ref "U16")
      (value "TPS5430DDAR")
      (footprint "ESOP-8_L4.9-W3.9-P1.27-LS6.0-TL-EP")
      (fields (field (name "MANUFACTURER") "TI(��������)"))
      (libsource (lib "FCU_Integrated_Library") (part "TPS5430DDAR"))
    )
    (comp (ref "USART2")
      (value "SH1.0-4")
      (footprint "飞控底板兼容版:SH_1.0_卧")
      (description "Header, 4-Pin")
      (fields (field (name "PUBLISHER") "Altium Limited"))
      (libsource (lib "Miscellaneous Connectors") (part "Header 4"))
    )
    (comp (ref "USART3")
      (value "SH1.0-4")
      (footprint "飞控底板兼容版:SH_1.0_卧")
      (description "Header, 4-Pin")
      (fields (field (name "PUBLISHER") "Altium Limited"))
      (libsource (lib "Miscellaneous Connectors") (part "Header 4"))
    )
    (comp (ref "USART4")
      (value "SH1.0-4")
      (footprint "飞控底板兼容版:SH_1.0_卧")
      (description "Header, 4-Pin")
      (fields (field (name "PUBLISHER") "Altium Limited"))
      (libsource (lib "Miscellaneous Connectors") (part "Header 4"))
    )
    (comp (ref "USART5")
      (value "SH1.0-4")
      (footprint "飞控底板兼容版:SH_1.0_卧")
      (description "Header, 4-Pin")
      (fields (field (name "PUBLISHER") "Altium Limited"))
      (libsource (lib "Miscellaneous Connectors") (part "Header 4"))
    )
    (comp (ref "USB0")
      (value "TYPE-C 16PIN 2MD(073)")
      (footprint "USB-C-SMD_TYPE-C-6PIN-2MD-073")
      (description "USB TYPE-C")
      (fields (field (name "MANUFACTURER") "SHOU HAN(�׺�)"))
      (libsource (lib "FCU_Integrated_Library") (part "TYPE-C 16PIN 2MD(073)"))
    )
    (comp (ref "Y1")
      (value "32.768KHz")
      (footprint "OSC 3215-2P")
      (description "Crystal 8MHz PLUG")
      (libsource (lib "*") (part "CRYSTAL"))
    )
    (comp (ref "Y2")
      (value "25MHz 9pF")
      (footprint "OSC-SMD_4P-L3.2-W2.5-BL")
      (description "Crystal 3225 25MHz")
      (fields (field (name "MANUFACTURER") "YJX(�ž���)") (field (name "MANUFACTURER PART") "TAXM8M4RDBCCT2T"))
      (libsource (lib "FCU_Integrated_Library") (part "TAXM8M4RDBCCT2T"))
    )
  )
  (nets
    (net (code "1") (name "/AK8975_CS") (class "Default")
      (node (ref "R202") (pin "1") (pinfunction "1_1") (pintype "passive"))
      (node (ref "U3") (pin "35") (pinfunction "PB1/T3_CH4_35") (pintype "passive"))
    )
    (net (code "2") (name "/AK8975_CSB") (class "Default")
      (node (ref "R202") (pin "2") (pinfunction "2_2") (pintype "passive"))
      (node (ref "U11") (pin "A2") (pinfunction "CSB_A2") (pintype "passive"))
    )
    (net (code "3") (name "/AK8975_DRDY") (class "Default")
      (node (ref "U11") (pin "C3") (pinfunction "DRDY_C3") (pintype "passive"))
    )
    (net (code "4") (name "/AK8975_SCL") (class "Default")
      (node (ref "R201") (pin "2") (pinfunction "2_2") (pintype "passive"))
      (node (ref "U11") (pin "A3") (pinfunction "SCL/SK_A3") (pintype "passive"))
    )
    (net (code "5") (name "/AK8975_SDA") (class "Default")
      (node (ref "R203") (pin "2") (pinfunction "2_2") (pintype "passive"))
      (node (ref "U11") (pin "D4") (pinfunction "SDA/SI_D4") (pintype "passive"))
    )
    (net (code "6") (name "/AK8975_SO") (class "Default")
      (node (ref "R204") (pin "2") (pinfunction "2_2") (pintype "passive"))
      (node (ref "U11") (pin "B4") (pinfunction "SO_B4") (pintype "passive"))
    )
    (net (code "7") (name "/AK09915_CS") (class "Default")
      (node (ref "R219") (pin "1") (pinfunction "1_1") (pintype "passive"))
      (node (ref "U3") (pin "36") (pinfunction "PB2_36") (pintype "passive"))
    )
    (net (code "8") (name "/AK09915_CS_2") (class "Default")
      (node (ref "R219") (pin "2") (pinfunction "2_2") (pintype "passive"))
      (node (ref "U15") (pin "A2") (pinfunction "CSB_A2") (pintype "passive"))
    )
    (net (code "9") (name "/AK09915_DRDY") (class "Default")
      (node (ref "U15") (pin "A1") (pinfunction "DRDY_A1") (pintype "passive"))
    )
    (net (code "10") (name "/AK09915_SCL") (class "Default")
      (node (ref "R218") (pin "2") (pinfunction "2_2") (pintype "passive"))
      (node (ref "U15") (pin "A3") (pinfunction "SCL/SK_A3") (pintype "passive"))
    )
    (net (code "11") (name "/AK09915_SDA") (class "Default")
      (node (ref "R221") (pin "2") (pinfunction "2_2") (pintype "passive"))
      (node (ref "U15") (pin "A4") (pinfunction "SDA/SI_A4") (pintype "passive"))
    )
    (net (code "12") (name "/AK09915_SO") (class "Default")
      (node (ref "R220") (pin "2") (pinfunction "2_2") (pintype "passive"))
      (node (ref "U15") (pin "B4") (pinfunction "SO_B4") (pintype "passive"))
    )
    (net (code "13") (name "/BAT_ADC") (class "Default")
      (node (ref "R53") (pin "1") (pinfunction "1_1") (pintype "passive"))
      (node (ref "U3") (pin "18") (pinfunction "PC3_C/ADC3_INP1_18") (pintype "passive"))
    )
    (net (code "14") (name "/BMI088_CS") (class "Default")
      (node (ref "R208") (pin "1") (pinfunction "1_1") (pintype "passive"))
      (node (ref "U3") (pin "34") (pinfunction "PB0/T3_CH3_34") (pintype "passive"))
    )
    (net (code "15") (name "/BMI088_CS1") (class "Default")
      (node (ref "R208") (pin "2") (pinfunction "2_2") (pintype "passive"))
      (node (ref "U8") (pin "14") (pinfunction "CSB1_14") (pintype "input"))
      (node (ref "U9") (pin "8") (pinfunction "CS1_8") (pintype "passive"))
    )
    (net (code "16") (name "/BMI088_CS2") (class "Default")
      (node (ref "R206") (pin "2") (pinfunction "2_2") (pintype "passive"))
      (node (ref "U8") (pin "5") (pinfunction "CSB2_5") (pintype "input"))
      (node (ref "U9") (pin "9") (pinfunction "CS2_9") (pintype "passive"))
    )
    (net (code "17") (name "/BMI088_CS_BKUP") (class "Default")
      (node (ref "R206") (pin "1") (pinfunction "1_1") (pintype "passive"))
      (node (ref "U3") (pin "32") (pinfunction "PC4_32") (pintype "passive"))
    )
    (net (code "18") (name "/BMI088_MISO") (class "Default")
      (node (ref "R207") (pin "2") (pinfunction "2_2") (pintype "passive"))
      (node (ref "U8") (pin "10") (pinfunction "SDO2_10") (pintype "output"))
      (node (ref "U8") (pin "15") (pinfunction "SDO1_15") (pintype "output"))
    )
    (net (code "19") (name "/BMI088_MOSI") (class "Default")
      (node (ref "R209") (pin "2") (pinfunction "2_2") (pintype "passive"))
      (node (ref "U8") (pin "9") (pinfunction "SDA/SDI_9") (pintype "bidirectional"))
    )
    (net (code "20") (name "/BMI088_SCK") (class "Default")
      (node (ref "R205") (pin "2") (pinfunction "2_2") (pintype "passive"))
      (node (ref "U8") (pin "8") (pinfunction "SCL/SCK_8") (pintype "input"))
    )
    (net (code "21") (name "/BOOT0") (class "Default")
      (node (ref "BOOT") (pin "2") (pinfunction "2_2") (pintype "passive"))
      (node (ref "R7") (pin "1") (pinfunction "1_1") (pintype "passive"))
      (node (ref "U3") (pin "94") (pinfunction "BOOT0_94") (pintype "passive"))
    )
    (net (code "22") (name "/GPS_RX") (class "Default")
      (node (ref "GPS_USART") (pin "4") (pinfunction "4_4") (pintype "passive"))
      (node (ref "R234") (pin "2") (pinfunction "2_2") (pintype "passive"))
    )
    (net (code "23") (name "/GPS_SCL") (class "Default")
      (node (ref "GPS_Compass") (pin "3") (pinfunction "3_3") (pintype "passive"))
      (node (ref "R235") (pin "2") (pinfunction "2_2") (pintype "passive"))
    )
    (net (code "24") (name "/GPS_SDA") (class "Default")
      (node (ref "GPS_Compass") (pin "4") (pinfunction "4_4") (pintype "passive"))
      (node (ref "R236") (pin "2") (pinfunction "2_2") (pintype "passive"))
    )
    (net (code "25") (name "/GPS_TX") (class "Default")
      (node (ref "GPS_USART") (pin "3") (pinfunction "3_3") (pintype "passive"))
      (node (ref "R233") (pin "2") (pinfunction "2_2") (pintype "passive"))
    )
    (net (code "26") (name "/I2C_EXT_SCL") (class "Default")
      (node (ref "R222") (pin "2") (pinfunction "2_2") (pintype "passive"))
      (node (ref "R235") (pin "1") (pinfunction "1_1") (pintype "passive"))
      (node (ref "R237") (pin "1") (pinfunction "1_1") (pintype "passive"))
      (node (ref "U3") (pin "59") (pinfunction "PD12/I2C4_SCL_59") (pintype "passive"))
    )
    (net (code "27") (name "/I2C_EXT_SDA") (class "Default")
      (node (ref "R223") (pin "2") (pinfunction "2_2") (pintype "passive"))
      (node (ref "R236") (pin "1") (pinfunction "1_1") (pintype "passive"))
      (node (ref "R238") (pin "1") (pinfunction "1_1") (pintype "passive"))
      (node (ref "U3") (pin "60") (pinfunction "PD13/I2C4_SDA_60") (pintype "passive"))
    )
    (net (code "28") (name "/I2C_OLED_SCL") (class "Default")
      (node (ref "OLED") (pin "2") (pinfunction "SCL_2") (pintype "bidirectional"))
      (node (ref "U3") (pin "42") (pinfunction "PE12/T1_CH3N/SPI4_SCK_42") (pintype "passive"))
    )
    (net (code "29") (name "/I2C_OLED_SDA") (class "Default")
      (node (ref "OLED") (pin "3") (pinfunction "SDA_3") (pintype "bidirectional"))
      (node (ref "U3") (pin "44") (pinfunction "PE14/T1_CH4/SPI4_MOSI_44") (pintype "passive"))
    )
    (net (code "30") (name "/ICM20602_CS") (class "Default")
      (node (ref "R213") (pin "2") (pinfunction "2_2") (pintype "passive"))
      (node (ref "U5") (pin "5") (pinfunction "CS_5") (pintype "passive"))
    )
    (net (code "31") (name "/ICM20602_CS_BKUP") (class "Default")
      (node (ref "R213") (pin "1") (pinfunction "1_1") (pintype "passive"))
      (node (ref "U3") (pin "33") (pinfunction "PC5_33") (pintype "passive"))
    )
    (net (code "32") (name "/ICM20602_FSY") (class "Default")
      (node (ref "U5") (pin "8") (pinfunction "FSYNC_8") (pintype "passive"))
    )
    (net (code "33") (name "/ICM20602_INT") (class "Default")
      (node (ref "R31") (pin "1") (pinfunction "1_1") (pintype "passive"))
      (node (ref "U5") (pin "6") (pinfunction "INT_6") (pintype "passive"))
      (node (ref "U9") (pin "7") (pinfunction "INT_7") (pintype "passive"))
    )
    (net (code "34") (name "/ICM20602_SA") (class "Default")
      (node (ref "R212") (pin "2") (pinfunction "2_2") (pintype "passive"))
      (node (ref "U5") (pin "4") (pinfunction "SA0/SDO_4") (pintype "passive"))
    )
    (net (code "35") (name "/ICM20602_SCL") (class "Default")
      (node (ref "R210") (pin "2") (pinfunction "2_2") (pintype "passive"))
      (node (ref "U5") (pin "2") (pinfunction "SCL/SPC_2") (pintype "passive"))
    )
    (net (code "36") (name "/ICM20602_SDA") (class "Default")
      (node (ref "R211") (pin "2") (pinfunction "2_2") (pintype "passive"))
      (node (ref "U5") (pin "3") (pinfunction "SDA/SDI_3") (pintype "passive"))
    )
    (net (code "37") (name "/KEY_2_PE3") (class "Default")
      (node (ref "R2") (pin "1") (pinfunction "1_1") (pintype "passive"))
      (node (ref "S1") (pin "2") (pinfunction "2_2") (pintype "passive"))
      (node (ref "U3") (pin "2") (pinfunction "PE3_2") (pintype "passive"))
    )
    (net (code "38") (name "/KEY_3_PD4") (class "Default")
      (node (ref "R4") (pin "1") (pinfunction "1_1") (pintype "passive"))
      (node (ref "S2") (pin "2") (pinfunction "2_2") (pintype "passive"))
      (node (ref "U3") (pin "85") (pinfunction "PD4_85") (pintype "passive"))
    )
    (net (code "39") (name "/LED_B") (class "Default")
      (node (ref "R40") (pin "2") (pinfunction "2_2") (pintype "passive"))
      (node (ref "U3") (pin "30") (pinfunction "PA6/SPI6_MISO/DCMI_PIXCLK_30") (pintype "passive"))
    )
    (net (code "40") (name "/LED_G") (class "Default")
      (node (ref "R42") (pin "2") (pinfunction "2_2") (pintype "passive"))
      (node (ref "U3") (pin "69") (pinfunction "PA10/US1_RX_69") (pintype "passive"))
    )
    (net (code "41") (name "/LED_R") (class "Default")
      (node (ref "R44") (pin "2") (pinfunction "2_2") (pintype "passive"))
      (node (ref "U3") (pin "67") (pinfunction "PA8/MCO1_67") (pintype "passive"))
    )
    (net (code "42") (name "/Motor_1") (class "Default")
      (node (ref "Motor_1") (pin "1") (pinfunction "1_1") (pintype "passive"))
      (node (ref "Motor_1_2") (pin "1") (pinfunction "1_1") (pintype "passive"))
      (node (ref "R243") (pin "2") (pinfunction "2_2") (pintype "passive"))
      (node (ref "R56") (pin "2") (pinfunction "2_2") (pintype "passive"))
    )
    (net (code "43") (name "/Motor_1_IO") (class "Default")
      (node (ref "R243") (pin "1") (pinfunction "1_1") (pintype "passive"))
      (node (ref "U3") (pin "23") (pinfunction "PA1/T2_CH2/T5_CH2/U4_RX_23") (pintype "passive"))
    )
    (net (code "44") (name "/Motor_2") (class "Default")
      (node (ref "Motor_1") (pin "2") (pinfunction "2_2") (pintype "passive"))
      (node (ref "Motor_1_2") (pin "3") (pinfunction "3_3") (pintype "passive"))
      (node (ref "R244") (pin "2") (pinfunction "2_2") (pintype "passive"))
      (node (ref "R57") (pin "2") (pinfunction "2_2") (pintype "passive"))
    )
    (net (code "45") (name "/Motor_2_IO") (class "Default")
      (node (ref "R244") (pin "1") (pinfunction "1_1") (pintype "passive"))
      (node (ref "U3") (pin "29") (pinfunction "PA5/SPI6_SCK_29") (pintype "passive"))
    )
    (net (code "46") (name "/Motor_3") (class "Default")
      (node (ref "Motor_1") (pin "3") (pinfunction "3_3") (pintype "passive"))
      (node (ref "Motor_1_2") (pin "5") (pinfunction "5_5") (pintype "passive"))
      (node (ref "R245") (pin "2") (pinfunction "2_2") (pintype "passive"))
      (node (ref "R58") (pin "2") (pinfunction "2_2") (pintype "passive"))
    )
    (net (code "47") (name "/Motor_3_IO") (class "Default")
      (node (ref "R245") (pin "1") (pinfunction "1_1") (pintype "passive"))
      (node (ref "U3") (pin "46") (pinfunction "PB10/T2_CH3/I2C2_SCL/US3_TX_46") (pintype "passive"))
    )
    (net (code "48") (name "/Motor_4") (class "Default")
      (node (ref "Motor_1") (pin "4") (pinfunction "4_4") (pintype "passive"))
      (node (ref "Motor_1_2") (pin "7") (pinfunction "7_7") (pintype "passive"))
      (node (ref "R246") (pin "2") (pinfunction "2_2") (pintype "passive"))
      (node (ref "R99") (pin "2") (pinfunction "2_2") (pintype "passive"))
    )
    (net (code "49") (name "/Motor_4_IO") (class "Default")
      (node (ref "R246") (pin "1") (pinfunction "1_1") (pintype "passive"))
      (node (ref "U3") (pin "47") (pinfunction "PB11/T2_CH4/I2C2_SDA/US3_RX_47") (pintype "passive"))
    )
    (net (code "50") (name "/Motor_5") (class "Default")
      (node (ref "Motor_1_2") (pin "2") (pinfunction "2_2") (pintype "passive"))
      (node (ref "Motor_2") (pin "1") (pinfunction "1_1") (pintype "passive"))
      (node (ref "R100") (pin "2") (pinfunction "2_2") (pintype "passive"))
      (node (ref "R247") (pin "2") (pinfunction "2_2") (pintype "passive"))
    )
    (net (code "51") (name "/Motor_5_IO") (class "Default")
      (node (ref "R247") (pin "1") (pinfunction "1_1") (pintype "passive"))
      (node (ref "U3") (pin "93") (pinfunction "PB7/I2C4_SDA_93") (pintype "passive"))
    )
    (net (code "52") (name "/Motor_6") (class "Default")
      (node (ref "Motor_1_2") (pin "4") (pinfunction "4_4") (pintype "passive"))
      (node (ref "Motor_2") (pin "2") (pinfunction "2_2") (pintype "passive"))
      (node (ref "R101") (pin "2") (pinfunction "2_2") (pintype "passive"))
      (node (ref "R248") (pin "2") (pinfunction "2_2") (pintype "passive"))
    )
    (net (code "53") (name "/Motor_6_IO") (class "Default")
      (node (ref "R248") (pin "1") (pinfunction "1_1") (pintype "passive"))
      (node (ref "U3") (pin "95") (pinfunction "PB8/I2C1_SCL/U4_RX/FDCAN1_RX_95") (pintype "passive"))
    )
    (net (code "54") (name "/Motor_7") (class "Default")
      (node (ref "Motor_1_2") (pin "6") (pinfunction "6_6") (pintype "passive"))
      (node (ref "Motor_2") (pin "3") (pinfunction "3_3") (pintype "passive"))
      (node (ref "R102") (pin "2") (pinfunction "2_2") (pintype "passive"))
      (node (ref "R249") (pin "2") (pinfunction "2_2") (pintype "passive"))
    )
    (net (code "55") (name "/Motor_7_IO") (class "Default")
      (node (ref "R249") (pin "1") (pinfunction "1_1") (pintype "passive"))
      (node (ref "U3") (pin "24") (pinfunction "PA2/T2_CH3/T5_CH3/US2_TX_24") (pintype "passive"))
    )
    (net (code "56") (name "/Motor_8") (class "Default")
      (node (ref "Motor_1_2") (pin "8") (pinfunction "8_8") (pintype "passive"))
      (node (ref "Motor_2") (pin "4") (pinfunction "4_4") (pintype "passive"))
      (node (ref "R103") (pin "2") (pinfunction "2_2") (pintype "passive"))
      (node (ref "R250") (pin "2") (pinfunction "2_2") (pintype "passive"))
    )
    (net (code "57") (name "/Motor_8_IO") (class "Default")
      (node (ref "R250") (pin "1") (pinfunction "1_1") (pintype "passive"))
      (node (ref "U3") (pin "25") (pinfunction "PA3/T2_CH4/T5_CH4/US2_RX_25") (pintype "passive"))
    )
    (net (code "58") (name "/PA0") (class "Default")
      (node (ref "R229") (pin "1") (pinfunction "1_1") (pintype "passive"))
      (node (ref "U3") (pin "22") (pinfunction "PA0/T2_CH1/T5_CH1/U4_TX_22") (pintype "passive"))
    )
    (net (code "59") (name "/PA4") (class "Default")
      (node (ref "U3") (pin "28") (pinfunction "PA4/SPI6_NSS/DCMI_HSYNC_28") (pintype "passive"))
    )
    (net (code "60") (name "/PA7") (class "Default")
      (node (ref "R49") (pin "1") (pinfunction "1_1") (pintype "passive"))
      (node (ref "U3") (pin "31") (pinfunction "PA7/SPI6_MOSI_31") (pintype "passive"))
    )
    (net (code "61") (name "/PA9") (class "Default")
      (node (ref "R201") (pin "1") (pinfunction "1_1") (pintype "passive"))
      (node (ref "R205") (pin "1") (pinfunction "1_1") (pintype "passive"))
      (node (ref "R210") (pin "1") (pinfunction "1_1") (pintype "passive"))
      (node (ref "R216") (pin "2") (pinfunction "2_2") (pintype "passive"))
      (node (ref "R218") (pin "1") (pinfunction "1_1") (pintype "passive"))
      (node (ref "R241") (pin "1") (pinfunction "1_1") (pintype "passive"))
      (node (ref "U3") (pin "68") (pinfunction "PA9/US1_TX_68") (pintype "passive"))
      (node (ref "U9") (pin "6") (pinfunction "CLK_6") (pintype "passive"))
    )
    (net (code "62") (name "/PA11") (class "Default")
      (node (ref "R5") (pin "1") (pinfunction "1_1") (pintype "passive"))
      (node (ref "U3") (pin "70") (pinfunction "PA11/OTG_FS_DM_70") (pintype "passive"))
    )
    (net (code "63") (name "/PA12") (class "Default")
      (node (ref "R6") (pin "1") (pinfunction "1_1") (pintype "passive"))
      (node (ref "U3") (pin "71") (pinfunction "PA12/OTG_FS_DP_71") (pintype "passive"))
    )
    (net (code "64") (name "/PA13") (class "Default")
      (node (ref "SWD") (pin "1") (pinfunction "1_1") (pintype "passive"))
      (node (ref "U3") (pin "72") (pinfunction "PA13/SWDIO_72") (pintype "passive"))
    )
    (net (code "65") (name "/PA14") (class "Default")
      (node (ref "SWD") (pin "3") (pinfunction "3_3") (pintype "passive"))
      (node (ref "U3") (pin "76") (pinfunction "PA14/SWCLK_76") (pintype "passive"))
    )
    (net (code "66") (name "/PA15") (class "Default")
      (node (ref "U3") (pin "77") (pinfunction "PA15_77") (pintype "passive"))
    )
    (net (code "67") (name "/PB3") (class "Default")
      (node (ref "U2") (pin "6") (pinfunction "CLK_6") (pintype "passive"))
      (node (ref "U3") (pin "89") (pinfunction "PB3/SPI1_SCK_89") (pintype "passive"))
    )
    (net (code "68") (name "/PB4") (class "Default")
      (node (ref "U2") (pin "2") (pinfunction "DO（IO1）_2") (pintype "passive"))
      (node (ref "U3") (pin "90") (pinfunction "PB4/SPI1_MISO_90") (pintype "passive"))
    )
    (net (code "69") (name "/PB5") (class "Default")
      (node (ref "U3") (pin "91") (pinfunction "PB5/SPI1_MOSI_91") (pintype "passive"))
    )
    (net (code "70") (name "/PB6") (class "Default")
      (node (ref "U3") (pin "92") (pinfunction "PB6/I2C4_SCL_92") (pintype "passive"))
    )
    (net (code "71") (name "/PB9") (class "Default")
      (node (ref "U3") (pin "96") (pinfunction "PB9/I2C1_SCL/U4_TX/FDCAN1_TX_96") (pintype "passive"))
    )
    (net (code "72") (name "/PB12") (class "Default")
      (node (ref "R232") (pin "1") (pinfunction "1_1") (pintype "passive"))
      (node (ref "U3") (pin "51") (pinfunction "PB12/SPI2_NSS/FDCAN2_RX_51") (pintype "passive"))
    )
    (net (code "73") (name "/PB13") (class "Default")
      (node (ref "R231") (pin "1") (pinfunction "1_1") (pintype "passive"))
      (node (ref "U3") (pin "52") (pinfunction "PB13/SPI2_SCK/FDCAN2_TX_52") (pintype "passive"))
    )
    (net (code "74") (name "/PB14") (class "Default")
      (node (ref "R233") (pin "1") (pinfunction "1_1") (pintype "passive"))
      (node (ref "U3") (pin "53") (pinfunction "PB14/SPI2_MISO_53") (pintype "passive"))
    )
    (net (code "75") (name "/PB15") (class "Default")
      (node (ref "R234") (pin "1") (pinfunction "1_1") (pintype "passive"))
      (node (ref "U3") (pin "54") (pinfunction "PB15/SPI2_MOSI_54") (pintype "passive"))
    )
    (net (code "76") (name "/PC0") (class "Default")
      (node (ref "U3") (pin "15") (pinfunction "PC0_15") (pintype "passive"))
    )
    (net (code "77") (name "/PC1") (class "Default")
      (node (ref "R203") (pin "1") (pinfunction "1_1") (pintype "passive"))
      (node (ref "R209") (pin "1") (pinfunction "1_1") (pintype "passive"))
      (node (ref "R211") (pin "1") (pinfunction "1_1") (pintype "passive"))
      (node (ref "R215") (pin "2") (pinfunction "2_2") (pintype "passive"))
      (node (ref "R221") (pin "1") (pinfunction "1_1") (pintype "passive"))
      (node (ref "R239") (pin "1") (pinfunction "1_1") (pintype "passive"))
      (node (ref "U3") (pin "16") (pinfunction "PC1_16") (pintype "passive"))
      (node (ref "U9") (pin "4") (pinfunction "MO_4") (pintype "passive"))
    )
    (net (code "78") (name "/PC2") (class "Default")
      (node (ref "R204") (pin "1") (pinfunction "1_1") (pintype "passive"))
      (node (ref "R207") (pin "1") (pinfunction "1_1") (pintype "passive"))
      (node (ref "R212") (pin "1") (pinfunction "1_1") (pintype "passive"))
      (node (ref "R217") (pin "2") (pinfunction "2_2") (pintype "passive"))
      (node (ref "R220") (pin "1") (pinfunction "1_1") (pintype "passive"))
      (node (ref "R240") (pin "1") (pinfunction "1_1") (pintype "passive"))
      (node (ref "U3") (pin "17") (pinfunction "PC2_C/ADC3_INP0_17") (pintype "passive"))
      (node (ref "U9") (pin "5") (pinfunction "MI_5") (pintype "passive"))
    )
    (net (code "79") (name "/PC6") (class "Default")
      (node (ref "U3") (pin "63") (pinfunction "PC6/T3_CH1/US6_TX/DCMI_D0_63") (pintype "passive"))
    )
    (net (code "80") (name "/PC7") (class "Default")
      (node (ref "Q3") (pin "1") (pinfunction "D_1") (pintype "passive"))
      (node (ref "R52") (pin "2") (pinfunction "2_2") (pintype "passive"))
      (node (ref "U3") (pin "64") (pinfunction "PC7/T3_CH2/US6_RX/DCMI_D1_64") (pintype "passive"))
    )
    (net (code "81") (name "/PC8") (class "Default")
      (node (ref "SD1") (pin "7") (pinfunction "DAT0_7") (pintype "passive"))
      (node (ref "U3") (pin "65") (pinfunction "PC8/SDMMC1_D0_65") (pintype "passive"))
    )
    (net (code "82") (name "/PC9") (class "Default")
      (node (ref "SD1") (pin "8") (pinfunction "DAT1_8") (pintype "passive"))
      (node (ref "U3") (pin "66") (pinfunction "PC9/SDMMC1_D1_66") (pintype "passive"))
    )
    (net (code "83") (name "/PC10") (class "Default")
      (node (ref "SD1") (pin "1") (pinfunction "DAT2_1") (pintype "passive"))
      (node (ref "U3") (pin "78") (pinfunction "PC10/SDMMC1_D2_78") (pintype "passive"))
    )
    (net (code "84") (name "/PC11") (class "Default")
      (node (ref "SD1") (pin "2") (pinfunction "CD/DAT3_2") (pintype "passive"))
      (node (ref "U3") (pin "79") (pinfunction "PC11/SDMMC1_D3_79") (pintype "passive"))
    )
    (net (code "85") (name "/PC12") (class "Default")
      (node (ref "SD1") (pin "5") (pinfunction "CLK_5") (pintype "passive"))
      (node (ref "U3") (pin "80") (pinfunction "PC12/SDMMC1_CK_80") (pintype "passive"))
    )
    (net (code "86") (name "/PC13") (class "Default")
      (node (ref "U3") (pin "7") (pinfunction "PC13/RTC_TAMP_1/RTC_TS_7") (pintype "passive"))
    )
    (net (code "87") (name "/PC14") (class "Default")
      (node (ref "C10") (pin "2") (pinfunction "2_2") (pintype "passive"))
      (node (ref "TP5") (pin "1") (pinfunction "1_1") (pintype "passive"))
      (node (ref "U3") (pin "8") (pinfunction "PC14/OS32_IN_8") (pintype "passive"))
      (node (ref "Y1") (pin "2") (pinfunction "2_2") (pintype "passive"))
    )
    (net (code "88") (name "/PC15") (class "Default")
      (node (ref "C11") (pin "2") (pinfunction "2_2") (pintype "passive"))
      (node (ref "TP6") (pin "1") (pinfunction "1_1") (pintype "passive"))
      (node (ref "U3") (pin "9") (pinfunction "PC15/OS32_OUT_9") (pintype "passive"))
      (node (ref "Y1") (pin "1") (pinfunction "1_1") (pintype "passive"))
    )
    (net (code "89") (name "/PD0") (class "Default")
      (node (ref "R230") (pin "1") (pinfunction "1_1") (pintype "passive"))
      (node (ref "U3") (pin "81") (pinfunction "PD0/U4_RX/FDCAN1_RX_81") (pintype "passive"))
    )
    (net (code "90") (name "/PD1") (class "Default")
      (node (ref "U3") (pin "82") (pinfunction "PD1/U4_TX/FDCAN1_TX_82") (pintype "passive"))
    )
    (net (code "91") (name "/PD2") (class "Default")
      (node (ref "SD1") (pin "3") (pinfunction "CMD_3") (pintype "passive"))
      (node (ref "U3") (pin "83") (pinfunction "PD2/SDMMC1_CMD_83") (pintype "passive"))
    )
    (net (code "92") (name "/PD3") (class "Default")
      (node (ref "U3") (pin "84") (pinfunction "PD3_84") (pintype "passive"))
    )
    (net (code "93") (name "/PD5") (class "Default")
      (node (ref "R225") (pin "1") (pinfunction "1_1") (pintype "passive"))
      (node (ref "U3") (pin "86") (pinfunction "PD5/US2_TX_86") (pintype "passive"))
    )
    (net (code "94") (name "/PD6") (class "Default")
      (node (ref "R226") (pin "1") (pinfunction "1_1") (pintype "passive"))
      (node (ref "U3") (pin "87") (pinfunction "PD6/US2_RX_87") (pintype "passive"))
    )
    (net (code "95") (name "/PD7") (class "Default")
      (node (ref "U2") (pin "5") (pinfunction "DI（IO0）_5") (pintype "passive"))
      (node (ref "U3") (pin "88") (pinfunction "PD7_88") (pintype "passive"))
    )
    (net (code "96") (name "/PD8") (class "Default")
      (node (ref "R227") (pin "1") (pinfunction "1_1") (pintype "passive"))
      (node (ref "U3") (pin "55") (pinfunction "PD8/US3_TX_55") (pintype "passive"))
    )
    (net (code "97") (name "/PD9") (class "Default")
      (node (ref "R228") (pin "1") (pinfunction "1_1") (pintype "passive"))
      (node (ref "U3") (pin "56") (pinfunction "PD9/US3_RX_56") (pintype "passive"))
    )
    (net (code "98") (name "/PD10") (class "Default")
      (node (ref "R91") (pin "1") (pinfunction "1_1") (pintype "passive"))
      (node (ref "U2") (pin "1") (pinfunction "CS#_1") (pintype "passive"))
      (node (ref "U3") (pin "57") (pinfunction "PD10_57") (pintype "passive"))
      (node (ref "U9") (pin "11") (pinfunction "CS4_11") (pintype "passive"))
    )
    (net (code "99") (name "/PD11") (class "Default")
      (node (ref "U3") (pin "58") (pinfunction "PD11_58") (pintype "passive"))
    )
    (net (code "100") (name "/PD14") (class "Default")
      (node (ref "U3") (pin "61") (pinfunction "PD14/T4_CH3_61") (pintype "passive"))
    )
    (net (code "101") (name "/PD15") (class "Default")
      (node (ref "U3") (pin "62") (pinfunction "PD15/T4_CH4_62") (pintype "passive"))
    )
    (net (code "102") (name "/PE0") (class "Default")
      (node (ref "U3") (pin "97") (pinfunction "PE0/U8_RX/DCMI_D2_97") (pintype "passive"))
    )
    (net (code "103") (name "/PE1") (class "Default")
      (node (ref "U3") (pin "98") (pinfunction "PE1/U8_TX/DCMI_D3_98") (pintype "passive"))
    )
    (net (code "104") (name "/PE2") (class "Default")
      (node (ref "U3") (pin "1") (pinfunction "PE2/SPI4_SCK_1") (pintype "passive"))
    )
    (net (code "105") (name "/PE4") (class "Default")
      (node (ref "U3") (pin "3") (pinfunction "PE4/SPI4_NSS/DCMI_D4_3") (pintype "passive"))
    )
    (net (code "106") (name "/PE5") (class "Default")
      (node (ref "U3") (pin "4") (pinfunction "PE5/SPI4_MISO/DCMI_D6_4") (pintype "passive"))
    )
    (net (code "107") (name "/PE6") (class "Default")
      (node (ref "U3") (pin "5") (pinfunction "PE6/SPI4_MOSI/DCMI_D7_5") (pintype "passive"))
    )
    (net (code "108") (name "/PE7") (class "Default")
      (node (ref "R242") (pin "1") (pinfunction "1_1") (pintype "passive"))
      (node (ref "U3") (pin "37") (pinfunction "PE7/U7_RX_37") (pintype "passive"))
    )
    (net (code "109") (name "/PE8") (class "Default")
      (node (ref "R214") (pin "2") (pinfunction "2_2") (pintype "passive"))
      (node (ref "U3") (pin "38") (pinfunction "PE8/U7_TX_38") (pintype "passive"))
    )
    (net (code "110") (name "/PE9") (class "Default")
      (node (ref "U3") (pin "39") (pinfunction "PE9/T1_CH1/U7_RTS_39") (pintype "passive"))
    )
    (net (code "111") (name "/PE10") (class "Default")
      (node (ref "R92") (pin "1") (pinfunction "1_1") (pintype "passive"))
      (node (ref "U3") (pin "40") (pinfunction "PE10/T1_CH2N/U7_CTS_40") (pintype "passive"))
    )
    (net (code "112") (name "/PE11") (class "Default")
      (node (ref "U3") (pin "41") (pinfunction "PE11/SPI4_NSS_41") (pintype "passive"))
    )
    (net (code "113") (name "/PE13") (class "Default")
      (node (ref "U3") (pin "43") (pinfunction "PE13/T1_CH3/SPI4_MISO_43") (pintype "passive"))
    )
    (net (code "114") (name "/PE15") (class "Default")
      (node (ref "U3") (pin "45") (pinfunction "PE15/FMC_D12/LCD_R7_45") (pintype "passive"))
    )
    (net (code "115") (name "/PH0") (class "Default")
      (node (ref "C12") (pin "1") (pinfunction "1_1") (pintype "passive"))
      (node (ref "R8") (pin "1") (pinfunction "1_1") (pintype "passive"))
      (node (ref "TP7") (pin "1") (pinfunction "1_1") (pintype "passive"))
      (node (ref "U3") (pin "12") (pinfunction "PH0/OSC_IN_12") (pintype "passive"))
      (node (ref "Y2") (pin "1") (pinfunction "1_1") (pintype "passive"))
    )
    (net (code "116") (name "/PH1") (class "Default")
      (node (ref "C13") (pin "2") (pinfunction "2_2") (pintype "passive"))
      (node (ref "R8") (pin "2") (pinfunction "2_2") (pintype "passive"))
      (node (ref "TP8") (pin "1") (pinfunction "1_1") (pintype "passive"))
      (node (ref "U3") (pin "13") (pinfunction "PH1/OSC_OUT_13") (pintype "passive"))
      (node (ref "Y2") (pin "3") (pinfunction "3_3") (pintype "passive"))
    )
    (net (code "117") (name "/QMC5883L_DRDY") (class "Default")
      (node (ref "U13") (pin "15") (pinfunction "DRDY_15") (pintype "passive"))
    )
    (net (code "118") (name "/QMC5883L_SCL") (class "Default")
      (node (ref "R222") (pin "1") (pinfunction "1_1") (pintype "passive"))
      (node (ref "R33") (pin "1") (pinfunction "1_1") (pintype "passive"))
      (node (ref "U13") (pin "1") (pinfunction "SCL_1") (pintype "passive"))
    )
    (net (code "119") (name "/QMC5883L_SDA") (class "Default")
      (node (ref "R223") (pin "1") (pinfunction "1_1") (pintype "passive"))
      (node (ref "R34") (pin "1") (pinfunction "1_1") (pintype "passive"))
      (node (ref "U13") (pin "16") (pinfunction "SDA_16") (pintype "passive"))
    )
    (net (code "120") (name "/QMC5883L_SETC") (class "Default")
      (node (ref "C32") (pin "1") (pinfunction "1_1") (pintype "passive"))
      (node (ref "U13") (pin "12") (pinfunction "SETC_12") (pintype "passive"))
    )
    (net (code "121") (name "/REST") (class "Default")
      (node (ref "C14") (pin "2") (pinfunction "2_2") (pintype "passive"))
      (node (ref "R90") (pin "2") (pinfunction "2_2") (pintype "passive"))
      (node (ref "S3") (pin "2") (pinfunction "2_2") (pintype "passive"))
      (node (ref "U3") (pin "14") (pinfunction "NRST_14") (pintype "passive"))
    )
    (net (code "122") (name "/SBUS_IN") (class "Default")
      (node (ref "R49") (pin "2") (pinfunction "2_2") (pintype "passive"))
      (node (ref "R50") (pin "2") (pinfunction "2_2") (pintype "passive"))
      (node (ref "RC_IN") (pin "1") (pinfunction "1_1") (pintype "passive"))
      (node (ref "RC_IN_4") (pin "3") (pinfunction "3_3") (pintype "passive"))
      (node (ref "RC_IN_4") (pin "4") (pinfunction "4_4") (pintype "passive"))
    )
    (net (code "123") (name "/SPI_EXT_CS") (class "Default")
      (node (ref "R242") (pin "2") (pinfunction "2_2") (pintype "passive"))
      (node (ref "SPI_External_2") (pin "4") (pinfunction "4_4") (pintype "passive"))
    )
    (net (code "124") (name "/SPI_EXT_MISO") (class "Default")
      (node (ref "R240") (pin "2") (pinfunction "2_2") (pintype "passive"))
      (node (ref "SPI_External_1") (pin "4") (pinfunction "4_4") (pintype "passive"))
    )
    (net (code "125") (name "/SPI_EXT_MOSI") (class "Default")
      (node (ref "R239") (pin "2") (pinfunction "2_2") (pintype "passive"))
      (node (ref "SPI_External_1") (pin "3") (pinfunction "3_3") (pintype "passive"))
    )
    (net (code "126") (name "/SPI_EXT_SCK") (class "Default")
      (node (ref "R241") (pin "2") (pinfunction "2_2") (pintype "passive"))
      (node (ref "SPI_External_2") (pin "3") (pinfunction "3_3") (pintype "passive"))
    )
    (net (code "127") (name "/SPL06_CS") (class "Default")
      (node (ref "R214") (pin "1") (pinfunction "1_1") (pintype "passive"))
      (node (ref "R28") (pin "1") (pinfunction "1_1") (pintype "passive"))
      (node (ref "U6") (pin "2") (pinfunction "CSB_2") (pintype "passive"))
      (node (ref "U9") (pin "10") (pinfunction "CS3_10") (pintype "passive"))
    )
    (net (code "128") (name "/SPL06_SCK") (class "Default")
      (node (ref "R216") (pin "1") (pinfunction "1_1") (pintype "passive"))
      (node (ref "R27") (pin "1") (pinfunction "1_1") (pintype "passive"))
      (node (ref "U6") (pin "4") (pinfunction "SCK_4") (pintype "passive"))
    )
    (net (code "129") (name "/SPL06_SDI") (class "Default")
      (node (ref "R215") (pin "1") (pinfunction "1_1") (pintype "passive"))
      (node (ref "R26") (pin "1") (pinfunction "1_1") (pintype "passive"))
      (node (ref "U6") (pin "3") (pinfunction "SDI_3") (pintype "passive"))
    )
    (net (code "130") (name "/SPL06_SDO") (class "Default")
      (node (ref "R217") (pin "1") (pinfunction "1_1") (pintype "passive"))
      (node (ref "R25") (pin "1") (pinfunction "1_1") (pintype "passive"))
      (node (ref "U6") (pin "5") (pinfunction "SDO_5") (pintype "passive"))
    )
    (net (code "131") (name "/TPS_PH") (class "Default")
      (node (ref "C42") (pin "1") (pinfunction "1_1") (pintype "passive"))
      (node (ref "D5") (pin "2") (pinfunction "K_2") (pintype "passive"))
      (node (ref "L1") (pin "1") (pinfunction "1_1") (pintype "passive"))
      (node (ref "U16") (pin "8") (pinfunction "PH_8") (pintype "passive"))
    )
    (net (code "132") (name "/TPS_VSENSE") (class "Default")
      (node (ref "R71") (pin "2") (pinfunction "2_2") (pintype "passive"))
      (node (ref "R72") (pin "1") (pinfunction "1_1") (pintype "passive"))
      (node (ref "U16") (pin "4") (pinfunction "VSENSE_4") (pintype "passive"))
    )
    (net (code "133") (name "/USB_DN") (class "Default")
      (node (ref "R5") (pin "2") (pinfunction "2_2") (pintype "passive"))
      (node (ref "USB0") (pin "5") (pinfunction "DN2_5") (pintype "passive"))
      (node (ref "USB0") (pin "7") (pinfunction "DN1_7") (pintype "passive"))
    )
    (net (code "134") (name "/USB_DP") (class "Default")
      (node (ref "R6") (pin "2") (pinfunction "2_2") (pintype "passive"))
      (node (ref "USB0") (pin "6") (pinfunction "DP1_6") (pintype "passive"))
      (node (ref "USB0") (pin "8") (pinfunction "DP2_8") (pintype "passive"))
    )
    (net (code "135") (name "/VBAT") (class "Default")
      (node (ref "R21") (pin "1") (pinfunction "1_1") (pintype "passive"))
      (node (ref "U3") (pin "6") (pinfunction "VBAT_6") (pintype "passive"))
    )
    (net (code "136") (name "/VBUS") (class "Default")
      (node (ref "F1") (pin "2") (pinfunction "2_2") (pintype "passive"))
      (node (ref "USB0") (pin "11") (pinfunction "VBUS_11") (pintype "passive"))
      (node (ref "USB0") (pin "2") (pinfunction "VBUS_2") (pintype "passive"))
    )
    (net (code "137") (name "/W25Qxx_Hold") (class "Default")
      (node (ref "R93") (pin "1") (pinfunction "1_1") (pintype "passive"))
      (node (ref "U2") (pin "3") (pinfunction "IO2_3") (pintype "passive"))
      (node (ref "U2") (pin "7") (pinfunction "IO3_7") (pintype "passive"))
    )
    (net (code "138") (name "3-6S") (class "Default")
      (node (ref "Bat_In") (pin "3") (pinfunction "3_3") (pintype "passive"))
      (node (ref "Bat_In") (pin "4") (pinfunction "4_4") (pintype "passive"))
      (node (ref "F0") (pin "1") (pinfunction "1_1") (pintype "passive"))
      (node (ref "J0") (pin "1") (pinfunction "1_1") (pintype "passive"))
      (node (ref "R54") (pin "1") (pinfunction "1_1") (pintype "passive"))
    )
    (net (code "139") (name "3V3") (class "Default")
      (node (ref "BOOT") (pin "1") (pinfunction "1_1") (pintype "passive"))
      (node (ref "C3") (pin "1") (pinfunction "1_1") (pintype "passive"))
      (node (ref "C5") (pin "1") (pinfunction "1_1") (pintype "passive"))
      (node (ref "C6") (pin "1") (pinfunction "1_1") (pintype "passive"))
      (node (ref "C7") (pin "1") (pinfunction "1_1") (pintype "passive"))
      (node (ref "C8") (pin "1") (pinfunction "1_1") (pintype "passive"))
      (node (ref "C81") (pin "1") (pinfunction "1_1") (pintype "passive"))
      (node (ref "C83") (pin "1") (pinfunction "1_1") (pintype "passive"))
      (node (ref "C9") (pin "1") (pinfunction "1_1") (pintype "passive"))
      (node (ref "R2") (pin "2") (pinfunction "2_2") (pintype "passive"))
      (node (ref "R21") (pin "2") (pinfunction "2_2") (pintype "passive"))
      (node (ref "R4") (pin "2") (pinfunction "2_2") (pintype "passive"))
      (node (ref "R52") (pin "1") (pinfunction "1_1") (pintype "passive"))
      (node (ref "R9") (pin "1") (pinfunction "1_1") (pintype "passive"))
      (node (ref "R90") (pin "1") (pinfunction "1_1") (pintype "passive"))
      (node (ref "R91") (pin "2") (pinfunction "2_2") (pintype "passive"))
      (node (ref "R93") (pin "2") (pinfunction "2_2") (pintype "passive"))
      (node (ref "SD1") (pin "4") (pinfunction "VDD_4") (pintype "passive"))
      (node (ref "SWD") (pin "4") (pinfunction "4_4") (pintype "passive"))
      (node (ref "U1") (pin "5") (pinfunction "OUT_5") (pintype "passive"))
      (node (ref "U2") (pin "8") (pinfunction "VCC_8") (pintype "passive"))
      (node (ref "U3") (pin "100") (pinfunction "VDD_100") (pintype "passive"))
      (node (ref "U3") (pin "11") (pinfunction "VDD_11") (pintype "passive"))
      (node (ref "U3") (pin "27") (pinfunction "VDD_27") (pintype "passive"))
      (node (ref "U3") (pin "50") (pinfunction "VDD_50") (pintype "passive"))
      (node (ref "U3") (pin "75") (pinfunction "VDD_75") (pintype "passive"))
    )
    (net (code "140") (name "5V") (class "Default")
      (node (ref "C1") (pin "1") (pinfunction "1_1") (pintype "passive"))
      (node (ref "C20") (pin "1") (pinfunction "1_1") (pintype "passive"))
      (node (ref "D0") (pin "1") (pinfunction "+_1") (pintype "passive"))
      (node (ref "D0") (pin "2") (pinfunction "+_2") (pintype "passive"))
      (node (ref "D0") (pin "3") (pinfunction "+_3") (pintype "passive"))
      (node (ref "D6") (pin "2") (pinfunction "K_2") (pintype "passive"))
      (node (ref "D7") (pin "1") (pinfunction "A_1") (pintype "passive"))
      (node (ref "F1") (pin "1") (pinfunction "1_1") (pintype "passive"))
      (node (ref "GPS_Compass") (pin "1") (pinfunction "1_1") (pintype "passive"))
      (node (ref "GPS_USART") (pin "1") (pinfunction "1_1") (pintype "passive"))
      (node (ref "I2C_External") (pin "1") (pinfunction "1_1") (pintype "passive"))
      (node (ref "OLED") (pin "1") (pinfunction "Vcc_1") (pintype "passive"))
      (node (ref "R100") (pin "1") (pinfunction "1_1") (pintype "passive"))
      (node (ref "R101") (pin "1") (pinfunction "1_1") (pintype "passive"))
      (node (ref "R102") (pin "1") (pinfunction "1_1") (pintype "passive"))
      (node (ref "R103") (pin "1") (pinfunction "1_1") (pintype "passive"))
      (node (ref "R56") (pin "1") (pinfunction "1_1") (pintype "passive"))
      (node (ref "R57") (pin "1") (pinfunction "1_1") (pintype "passive"))
      (node (ref "R58") (pin "1") (pinfunction "1_1") (pintype "passive"))
      (node (ref "R99") (pin "1") (pinfunction "1_1") (pintype "passive"))
      (node (ref "RC_IN") (pin "2") (pinfunction "2_2") (pintype "passive"))
      (node (ref "RC_IN_4") (pin "1") (pinfunction "1_1") (pintype "passive"))
      (node (ref "SPI_External_1") (pin "1") (pinfunction "1_1") (pintype "passive"))
      (node (ref "SPI_External_2") (pin "1") (pinfunction "1_1") (pintype "passive"))
      (node (ref "U1") (pin "1") (pinfunction "IN_1") (pintype "passive"))
      (node (ref "U1") (pin "3") (pinfunction "EN_3") (pintype "passive"))
      (node (ref "U10") (pin "1") (pinfunction "IN_1") (pintype "passive"))
      (node (ref "U10") (pin "3") (pinfunction "EN_3") (pintype "passive"))
      (node (ref "U9") (pin "2") (pinfunction "5V_2") (pintype "passive"))
      (node (ref "USART2") (pin "1") (pinfunction "1_1") (pintype "passive"))
      (node (ref "USART3") (pin "1") (pinfunction "1_1") (pintype "passive"))
      (node (ref "USART4") (pin "1") (pinfunction "1_1") (pintype "passive"))
      (node (ref "USART5") (pin "1") (pinfunction "1_1") (pintype "passive"))
    )
    (net (code "141") (name "BAT-") (class "Default")
      (node (ref "Bat_In") (pin "1") (pinfunction "1_1") (pintype "passive"))
      (node (ref "Bat_In") (pin "2") (pinfunction "2_2") (pintype "passive"))
      (node (ref "C40") (pin "2") (pinfunction "2_2") (pintype "passive"))
      (node (ref "C41") (pin "2") (pinfunction "2_2") (pintype "passive"))
      (node (ref "C43") (pin "1") (pinfunction "1_1") (pintype "passive"))
      (node (ref "C44") (pin "1") (pinfunction "1_1") (pintype "passive"))
      (node (ref "C55") (pin "2") (pinfunction "2_2") (pintype "passive"))
      (node (ref "D3") (pin "1") (pinfunction "A_1") (pintype "passive"))
      (node (ref "D5") (pin "1") (pinfunction "A_1") (pintype "passive"))
      (node (ref "J0") (pin "2") (pinfunction "2_2") (pintype "passive"))
      (node (ref "R55") (pin "2") (pinfunction "2_2") (pintype "passive"))
      (node (ref "R72") (pin "2") (pinfunction "2_2") (pintype "passive"))
      (node (ref "R81") (pin "2") (pinfunction "2_2") (pintype "passive"))
      (node (ref "R82") (pin "2") (pinfunction "2_2") (pintype "passive"))
      (node (ref "R83") (pin "2") (pinfunction "2_2") (pintype "passive"))
      (node (ref "R84") (pin "2") (pinfunction "2_2") (pintype "passive"))
      (node (ref "U16") (pin "6") (pinfunction "GND_6") (pintype "passive"))
      (node (ref "U16") (pin "9") (pinfunction "PowerPAD_9") (pintype "passive"))
    )
    (net (code "142") (name "GND") (class "Default")
      (node (ref "BOOT") (pin "3") (pinfunction "3_3") (pintype "passive"))
      (node (ref "C1") (pin "2") (pinfunction "2_2") (pintype "passive"))
      (node (ref "C10") (pin "1") (pinfunction "1_1") (pintype "passive"))
      (node (ref "C11") (pin "1") (pinfunction "1_1") (pintype "passive"))
      (node (ref "C12") (pin "2") (pinfunction "2_2") (pintype "passive"))
      (node (ref "C13") (pin "1") (pinfunction "1_1") (pintype "passive"))
      (node (ref "C14") (pin "1") (pinfunction "1_1") (pintype "passive"))
      (node (ref "C15") (pin "1") (pinfunction "1_1") (pintype "passive"))
      (node (ref "C16") (pin "2") (pinfunction "2_2") (pintype "passive"))
      (node (ref "C17") (pin "2") (pinfunction "2_2") (pintype "passive"))
      (node (ref "C18") (pin "2") (pinfunction "2_2") (pintype "passive"))
      (node (ref "C2") (pin "2") (pinfunction "2_2") (pintype "passive"))
      (node (ref "C20") (pin "2") (pinfunction "2_2") (pintype "passive"))
      (node (ref "C21") (pin "2") (pinfunction "2_2") (pintype "passive"))
      (node (ref "C22") (pin "2") (pinfunction "2_2") (pintype "passive"))
      (node (ref "C23") (pin "2") (pinfunction "2_2") (pintype "passive"))
      (node (ref "C24") (pin "2") (pinfunction "2_2") (pintype "passive"))
      (node (ref "C25") (pin "2") (pinfunction "2_2") (pintype "passive"))
      (node (ref "C26") (pin "2") (pinfunction "2_2") (pintype "passive"))
      (node (ref "C28") (pin "2") (pinfunction "2_2") (pintype "passive"))
      (node (ref "C29") (pin "2") (pinfunction "2_2") (pintype "passive"))
      (node (ref "C3") (pin "2") (pinfunction "2_2") (pintype "passive"))
      (node (ref "C30") (pin "2") (pinfunction "2_2") (pintype "passive"))
      (node (ref "C31") (pin "1") (pinfunction "1_1") (pintype "passive"))
      (node (ref "C35") (pin "2") (pinfunction "2_2") (pintype "passive"))
      (node (ref "C36") (pin "2") (pinfunction "2_2") (pintype "passive"))
      (node (ref "C37") (pin "2") (pinfunction "2_2") (pintype "passive"))
      (node (ref "C5") (pin "2") (pinfunction "2_2") (pintype "passive"))
      (node (ref "C51") (pin "2") (pinfunction "2_2") (pintype "passive"))
      (node (ref "C52") (pin "2") (pinfunction "2_2") (pintype "passive"))
      (node (ref "C6") (pin "2") (pinfunction "2_2") (pintype "passive"))
      (node (ref "C7") (pin "2") (pinfunction "2_2") (pintype "passive"))
      (node (ref "C8") (pin "2") (pinfunction "2_2") (pintype "passive"))
      (node (ref "C81") (pin "2") (pinfunction "2_2") (pintype "passive"))
      (node (ref "C83") (pin "2") (pinfunction "2_2") (pintype "passive"))
      (node (ref "C9") (pin "2") (pinfunction "2_2") (pintype "passive"))
      (node (ref "GND") (pin "1") (pinfunction "1_1") (pintype "passive"))
      (node (ref "GND") (pin "2") (pinfunction "2_2") (pintype "passive"))
      (node (ref "GND") (pin "3") (pinfunction "3_3") (pintype "passive"))
      (node (ref "GND") (pin "4") (pinfunction "4_4") (pintype "passive"))
      (node (ref "GPS_Compass") (pin "2") (pinfunction "2_2") (pintype "passive"))
      (node (ref "GPS_USART") (pin "2") (pinfunction "2_2") (pintype "passive"))
      (node (ref "I2C_External") (pin "2") (pinfunction "2_2") (pintype "passive"))
      (node (ref "Motor_1_2_GB") (pin "1") (pinfunction "1_1") (pintype "passive"))
      (node (ref "Motor_1_2_GB") (pin "2") (pinfunction "2_2") (pintype "passive"))
      (node (ref "Motor_1_2_GB") (pin "3") (pinfunction "3_3") (pintype "passive"))
      (node (ref "Motor_1_2_GB") (pin "4") (pinfunction "4_4") (pintype "passive"))
      (node (ref "OLED") (pin "0") (pinfunction "GND_0") (pintype "passive"))
      (node (ref "Q0") (pin "3") (pinfunction "S_3") (pintype "passive"))
      (node (ref "Q1") (pin "3") (pinfunction "S_3") (pintype "passive"))
      (node (ref "Q2") (pin "3") (pinfunction "S_3") (pintype "passive"))
      (node (ref "Q3") (pin "3") (pinfunction "S_3") (pintype "passive"))
      (node (ref "R41") (pin "2") (pinfunction "2_2") (pintype "passive"))
      (node (ref "R43") (pin "2") (pinfunction "2_2") (pintype "passive"))
      (node (ref "R45") (pin "2") (pinfunction "2_2") (pintype "passive"))
      (node (ref "R51") (pin "2") (pinfunction "2_2") (pintype "passive"))
      (node (ref "R7") (pin "2") (pinfunction "2_2") (pintype "passive"))
      (node (ref "R81") (pin "1") (pinfunction "1_1") (pintype "passive"))
      (node (ref "R82") (pin "1") (pinfunction "1_1") (pintype "passive"))
      (node (ref "R83") (pin "1") (pinfunction "1_1") (pintype "passive"))
      (node (ref "RC_IN") (pin "3") (pinfunction "3_3") (pintype "passive"))
      (node (ref "RC_IN_4") (pin "2") (pinfunction "2_2") (pintype "passive"))
      (node (ref "S1") (pin "1") (pinfunction "1_1") (pintype "passive"))
      (node (ref "S2") (pin "1") (pinfunction "1_1") (pintype "passive"))
      (node (ref "S3") (pin "1") (pinfunction "1_1") (pintype "passive"))
      (node (ref "SD1") (pin "10") (pinfunction "GND_10") (pintype "passive"))
      (node (ref "SD1") (pin "11") (pinfunction "GND_11") (pintype "passive"))
      (node (ref "SD1") (pin "12") (pinfunction "GND_12") (pintype "passive"))
      (node (ref "SD1") (pin "13") (pinfunction "GND_13") (pintype "passive"))
      (node (ref "SD1") (pin "6") (pinfunction "VSS_6") (pintype "passive"))
      (node (ref "SPI_External_1") (pin "2") (pinfunction "2_2") (pintype "passive"))
      (node (ref "SPI_External_2") (pin "2") (pinfunction "2_2") (pintype "passive"))
      (node (ref "SWD") (pin "2") (pinfunction "2_2") (pintype "passive"))
      (node (ref "U1") (pin "2") (pinfunction "GND_2") (pintype "passive"))
      (node (ref "U10") (pin "2") (pinfunction "GND_2") (pintype "passive"))
      (node (ref "U11") (pin "C1") (pinfunction "VSS_C1") (pintype "passive"))
      (node (ref "U11") (pin "D1") (pinfunction "CAD0_D1") (pintype "passive"))
      (node (ref "U11") (pin "D2") (pinfunction "CAD1_D2") (pintype "passive"))
      (node (ref "U13") (pin "11") (pinfunction "GND_11") (pintype "passive"))
      (node (ref "U13") (pin "9") (pinfunction "GND_9") (pintype "passive"))
      (node (ref "U15") (pin "C1") (pinfunction "VSS_C1") (pintype "passive"))
      (node (ref "U15") (pin "D1") (pinfunction "CAD0_D1") (pintype "passive"))
      (node (ref "U15") (pin "D2") (pinfunction "CAD1_D2") (pintype "passive"))
      (node (ref "U2") (pin "4") (pinfunction "GND_4") (pintype "passive"))
      (node (ref "U3") (pin "10") (pinfunction "VSS_10") (pintype "passive"))
      (node (ref "U3") (pin "19") (pinfunction "VSSA_19") (pintype "passive"))
      (node (ref "U3") (pin "26") (pinfunction "VSS_26") (pintype "passive"))
      (node (ref "U3") (pin "49") (pinfunction "VSS_49") (pintype "passive"))
      (node (ref "U3") (pin "74") (pinfunction "VSS_74") (pintype "passive"))
      (node (ref "U3") (pin "99") (pinfunction "VSS_99") (pintype "passive"))
      (node (ref "U5") (pin "10") (pinfunction "RESV_10") (pintype "passive"))
      (node (ref "U5") (pin "11") (pinfunction "RESV_11") (pintype "passive"))
      (node (ref "U5") (pin "12") (pinfunction "RESV_12") (pintype "passive"))
      (node (ref "U5") (pin "13") (pinfunction "GND_13") (pintype "passive"))
      (node (ref "U5") (pin "15") (pinfunction "RESV_15") (pintype "passive"))
      (node (ref "U5") (pin "9") (pinfunction "RESV_9") (pintype "passive"))
      (node (ref "U6") (pin "1") (pinfunction "GND_1") (pintype "passive"))
      (node (ref "U6") (pin "7") (pinfunction "GND_7") (pintype "passive"))
      (node (ref "U8") (pin "2") (pinfunction "NC_2") (pintype "passive"))
      (node (ref "U8") (pin "4") (pinfunction "GNDA_4") (pintype "passive"))
      (node (ref "U8") (pin "6") (pinfunction "GNDIO_6") (pintype "passive"))
      (node (ref "U8") (pin "7") (pinfunction "PS_7") (pintype "input"))
      (node (ref "U9") (pin "1") (pinfunction "GND_1") (pintype "passive"))
      (node (ref "U9") (pin "12") (pinfunction "GND_12") (pintype "passive"))
      (node (ref "USART2") (pin "2") (pinfunction "2_2") (pintype "passive"))
      (node (ref "USART3") (pin "2") (pinfunction "2_2") (pintype "passive"))
      (node (ref "USART4") (pin "2") (pinfunction "2_2") (pintype "passive"))
      (node (ref "USART5") (pin "2") (pinfunction "2_2") (pintype "passive"))
      (node (ref "USB0") (pin "1") (pinfunction "GND_1") (pintype "passive"))
      (node (ref "USB0") (pin "12") (pinfunction "GND_12") (pintype "passive"))
      (node (ref "USB0") (pin "13") (pinfunction "SHELL_13") (pintype "passive"))
      (node (ref "USB0") (pin "14") (pinfunction "SHELL_14") (pintype "passive"))
      (node (ref "Y2") (pin "2") (pinfunction "2_2") (pintype "passive"))
      (node (ref "Y2") (pin "4") (pinfunction "4_4") (pintype "passive"))
    )
    (net (code "143") (name "IMU_3V3") (class "Default")
      (node (ref "C22") (pin "1") (pinfunction "1_1") (pintype "passive"))
      (node (ref "C23") (pin "1") (pinfunction "1_1") (pintype "passive"))
      (node (ref "C24") (pin "1") (pinfunction "1_1") (pintype "passive"))
      (node (ref "C25") (pin "1") (pinfunction "1_1") (pintype "passive"))
      (node (ref "C26") (pin "1") (pinfunction "1_1") (pintype "passive"))
      (node (ref "C29") (pin "1") (pinfunction "1_1") (pintype "passive"))
      (node (ref "C30") (pin "1") (pinfunction "1_1") (pintype "passive"))
      (node (ref "C35") (pin "1") (pinfunction "1_1") (pintype "passive"))
      (node (ref "C36") (pin "1") (pinfunction "1_1") (pintype "passive"))
      (node (ref "C37") (pin "1") (pinfunction "1_1") (pintype "passive"))
      (node (ref "C51") (pin "1") (pinfunction "1_1") (pintype "passive"))
      (node (ref "C52") (pin "1") (pinfunction "1_1") (pintype "passive"))
      (node (ref "R25") (pin "2") (pinfunction "2_2") (pintype "passive"))
      (node (ref "R26") (pin "2") (pinfunction "2_2") (pintype "passive"))
      (node (ref "R27") (pin "2") (pinfunction "2_2") (pintype "passive"))
      (node (ref "R28") (pin "2") (pinfunction "2_2") (pintype "passive"))
      (node (ref "R31") (pin "2") (pinfunction "2_2") (pintype "passive"))
      (node (ref "R33") (pin "2") (pinfunction "2_2") (pintype "passive"))
      (node (ref "R34") (pin "2") (pinfunction "2_2") (pintype "passive"))
      (node (ref "U10") (pin "5") (pinfunction "OUT_5") (pintype "passive"))
      (node (ref "U11") (pin "B1") (pinfunction "VDD_B1") (pintype "passive"))
      (node (ref "U11") (pin "C4") (pinfunction "VID_C4") (pintype "passive"))
      (node (ref "U13") (pin "13") (pinfunction "VDDIO_13") (pintype "passive"))
      (node (ref "U13") (pin "2") (pinfunction "VDD_2") (pintype "passive"))
      (node (ref "U13") (pin "4") (pinfunction "S1_4") (pintype "passive"))
      (node (ref "U15") (pin "B1") (pinfunction "VDD_B1") (pintype "passive"))
      (node (ref "U15") (pin "C4") (pinfunction "VID_C4") (pintype "passive"))
      (node (ref "U15") (pin "D4") (pinfunction "RSTN_D4") (pintype "passive"))
      (node (ref "U5") (pin "1") (pinfunction "VDDIO_1") (pintype "passive"))
      (node (ref "U5") (pin "16") (pinfunction "VDD_16") (pintype "passive"))
      (node (ref "U6") (pin "6") (pinfunction "VddIO_6") (pintype "passive"))
      (node (ref "U6") (pin "8") (pinfunction "Vdd_8") (pintype "passive"))
      (node (ref "U8") (pin "11") (pinfunction "VDDIO_11") (pintype "passive"))
      (node (ref "U8") (pin "3") (pinfunction "VDD_3") (pintype "passive"))
    )
    (net (code "144") (name "Net-(C15-Pad2)") (class "Default")
      (node (ref "C15") (pin "2") (pinfunction "2_2") (pintype "passive"))
      (node (ref "U3") (pin "73") (pinfunction "VCAP_73") (pintype "passive"))
    )
    (net (code "145") (name "Net-(C18-Pad1)") (class "Default")
      (node (ref "C18") (pin "1") (pinfunction "1_1") (pintype "passive"))
      (node (ref "U3") (pin "48") (pinfunction "VCAP_48") (pintype "passive"))
    )
    (net (code "146") (name "Net-(C55-Pad1)") (class "Default")
      (node (ref "C55") (pin "1") (pinfunction "1_1") (pintype "passive"))
      (node (ref "R53") (pin "2") (pinfunction "2_2") (pintype "passive"))
      (node (ref "R54") (pin "2") (pinfunction "2_2") (pintype "passive"))
      (node (ref "R55") (pin "1") (pinfunction "1_1") (pintype "passive"))
    )
    (net (code "147") (name "Net-(D0---Pad4)") (class "Default")
      (node (ref "D0") (pin "4") (pinfunction "-_4") (pintype "passive"))
      (node (ref "R46") (pin "1") (pinfunction "1_1") (pintype "passive"))
    )
    (net (code "148") (name "Net-(D0---Pad5)") (class "Default")
      (node (ref "D0") (pin "5") (pinfunction "-_5") (pintype "passive"))
      (node (ref "R47") (pin "1") (pinfunction "1_1") (pintype "passive"))
    )
    (net (code "149") (name "Net-(D0---Pad6)") (class "Default")
      (node (ref "D0") (pin "6") (pinfunction "-_6") (pintype "passive"))
      (node (ref "R48") (pin "1") (pinfunction "1_1") (pintype "passive"))
    )
    (net (code "150") (name "Net-(D6-A)") (class "Default")
      (node (ref "C43") (pin "2") (pinfunction "2_2") (pintype "passive"))
      (node (ref "C44") (pin "2") (pinfunction "2_2") (pintype "passive"))
      (node (ref "D6") (pin "1") (pinfunction "A_1") (pintype "passive"))
      (node (ref "L1") (pin "2") (pinfunction "2_2") (pintype "passive"))
      (node (ref "R71") (pin "1") (pinfunction "1_1") (pintype "passive"))
    )
    (net (code "151") (name "Net-(D7-K)") (class "Default")
      (node (ref "D7") (pin "2") (pinfunction "K_2") (pintype "passive"))
      (node (ref "R84") (pin "1") (pinfunction "1_1") (pintype "passive"))
    )
    (net (code "152") (name "Net-(I2C_External-Pad3)") (class "Default")
      (node (ref "I2C_External") (pin "3") (pinfunction "3_3") (pintype "passive"))
      (node (ref "R237") (pin "2") (pinfunction "2_2") (pintype "passive"))
    )
    (net (code "153") (name "Net-(I2C_External-Pad4)") (class "Default")
      (node (ref "I2C_External") (pin "4") (pinfunction "4_4") (pintype "passive"))
      (node (ref "R238") (pin "2") (pinfunction "2_2") (pintype "passive"))
    )
    (net (code "154") (name "Net-(Q0-D)") (class "Default")
      (node (ref "Q0") (pin "1") (pinfunction "D_1") (pintype "passive"))
      (node (ref "R46") (pin "2") (pinfunction "2_2") (pintype "passive"))
    )
    (net (code "155") (name "Net-(Q0-G)") (class "Default")
      (node (ref "Q0") (pin "2") (pinfunction "G_2") (pintype "passive"))
      (node (ref "R40") (pin "1") (pinfunction "1_1") (pintype "passive"))
      (node (ref "R41") (pin "1") (pinfunction "1_1") (pintype "passive"))
    )
    (net (code "156") (name "Net-(Q1-D)") (class "Default")
      (node (ref "Q1") (pin "1") (pinfunction "D_1") (pintype "passive"))
      (node (ref "R47") (pin "2") (pinfunction "2_2") (pintype "passive"))
    )
    (net (code "157") (name "Net-(Q1-G)") (class "Default")
      (node (ref "Q1") (pin "2") (pinfunction "G_2") (pintype "passive"))
      (node (ref "R42") (pin "1") (pinfunction "1_1") (pintype "passive"))
      (node (ref "R43") (pin "1") (pinfunction "1_1") (pintype "passive"))
    )
    (net (code "158") (name "Net-(Q2-D)") (class "Default")
      (node (ref "Q2") (pin "1") (pinfunction "D_1") (pintype "passive"))
      (node (ref "R48") (pin "2") (pinfunction "2_2") (pintype "passive"))
    )
    (net (code "159") (name "Net-(Q2-G)") (class "Default")
      (node (ref "Q2") (pin "2") (pinfunction "G_2") (pintype "passive"))
      (node (ref "R44") (pin "1") (pinfunction "1_1") (pintype "passive"))
      (node (ref "R45") (pin "1") (pinfunction "1_1") (pintype "passive"))
    )
    (net (code "160") (name "Net-(Q3-G)") (class "Default")
      (node (ref "Q3") (pin "2") (pinfunction "G_2") (pintype "passive"))
      (node (ref "R50") (pin "1") (pinfunction "1_1") (pintype "passive"))
      (node (ref "R51") (pin "1") (pinfunction "1_1") (pintype "passive"))
    )
    (net (code "161") (name "Net-(R225-Pad2)") (class "Default")
      (node (ref "R225") (pin "2") (pinfunction "2_2") (pintype "passive"))
      (node (ref "USART2") (pin "3") (pinfunction "3_3") (pintype "passive"))
    )
    (net (code "162") (name "Net-(R226-Pad2)") (class "Default")
      (node (ref "R226") (pin "2") (pinfunction "2_2") (pintype "passive"))
      (node (ref "USART2") (pin "4") (pinfunction "4_4") (pintype "passive"))
    )
    (net (code "163") (name "Net-(R227-Pad2)") (class "Default")
      (node (ref "R227") (pin "2") (pinfunction "2_2") (pintype "passive"))
      (node (ref "USART3") (pin "3") (pinfunction "3_3") (pintype "passive"))
    )
    (net (code "164") (name "Net-(R228-Pad2)") (class "Default")
      (node (ref "R228") (pin "2") (pinfunction "2_2") (pintype "passive"))
      (node (ref "USART3") (pin "4") (pinfunction "4_4") (pintype "passive"))
    )
    (net (code "165") (name "Net-(R229-Pad2)") (class "Default")
      (node (ref "R229") (pin "2") (pinfunction "2_2") (pintype "passive"))
      (node (ref "USART4") (pin "3") (pinfunction "3_3") (pintype "passive"))
    )
    (net (code "166") (name "Net-(R230-Pad2)") (class "Default")
      (node (ref "R230") (pin "2") (pinfunction "2_2") (pintype "passive"))
      (node (ref "USART4") (pin "4") (pinfunction "4_4") (pintype "passive"))
    )
    (net (code "167") (name "Net-(R231-Pad2)") (class "Default")
      (node (ref "R231") (pin "2") (pinfunction "2_2") (pintype "passive"))
      (node (ref "USART5") (pin "3") (pinfunction "3_3") (pintype "passive"))
    )
    (net (code "168") (name "Net-(R232-Pad2)") (class "Default")
      (node (ref "R232") (pin "2") (pinfunction "2_2") (pintype "passive"))
      (node (ref "USART5") (pin "4") (pinfunction "4_4") (pintype "passive"))
    )
    (net (code "169") (name "Net-(U1-BYP)") (class "Default")
      (node (ref "C2") (pin "1") (pinfunction "1_1") (pintype "passive"))
      (node (ref "U1") (pin "4") (pinfunction "BYP_4") (pintype "passive"))
    )
    (net (code "170") (name "Net-(U5-REGOUT)") (class "Default")
      (node (ref "C28") (pin "1") (pinfunction "1_1") (pintype "passive"))
      (node (ref "U5") (pin "14") (pinfunction "REGOUT_14") (pintype "passive"))
    )
    (net (code "171") (name "Net-(U9-HT)") (class "Default")
      (node (ref "R92") (pin "2") (pinfunction "2_2") (pintype "passive"))
      (node (ref "U9") (pin "3") (pinfunction "HT_3") (pintype "passive"))
    )
    (net (code "172") (name "Net-(U10-BYP)") (class "Default")
      (node (ref "C21") (pin "1") (pinfunction "1_1") (pintype "passive"))
      (node (ref "U10") (pin "4") (pinfunction "BYP_4") (pintype "passive"))
    )
    (net (code "173") (name "Net-(U13-C1)") (class "Default")
      (node (ref "C31") (pin "2") (pinfunction "2_2") (pintype "passive"))
      (node (ref "U13") (pin "10") (pinfunction "C1_10") (pintype "passive"))
    )
    (net (code "174") (name "Net-(U13-SETP)") (class "Default")
      (node (ref "C32") (pin "2") (pinfunction "2_2") (pintype "passive"))
      (node (ref "U13") (pin "8") (pinfunction "SETP_8") (pintype "passive"))
    )
    (net (code "175") (name "Net-(U16-BOOT)") (class "Default")
      (node (ref "C42") (pin "2") (pinfunction "2_2") (pintype "passive"))
      (node (ref "U16") (pin "1") (pinfunction "BOOT_1") (pintype "passive"))
    )
    (net (code "176") (name "TPS_Vin") (class "Default")
      (node (ref "C40") (pin "1") (pinfunction "1_1") (pintype "passive"))
      (node (ref "C41") (pin "1") (pinfunction "1_1") (pintype "passive"))
      (node (ref "D3") (pin "2") (pinfunction "K_2") (pintype "passive"))
      (node (ref "F0") (pin "2") (pinfunction "2_2") (pintype "passive"))
      (node (ref "U16") (pin "7") (pinfunction "VIN_7") (pintype "passive"))
    )
    (net (code "177") (name "VDDA") (class "Default")
      (node (ref "C16") (pin "1") (pinfunction "1_1") (pintype "passive"))
      (node (ref "R10") (pin "1") (pinfunction "1_1") (pintype "passive"))
      (node (ref "R9") (pin "2") (pinfunction "2_2") (pintype "passive"))
      (node (ref "U3") (pin "21") (pinfunction "VDDA_21") (pintype "passive"))
    )
    (net (code "178") (name "VREF+") (class "Default")
      (node (ref "C17") (pin "1") (pinfunction "1_1") (pintype "passive"))
      (node (ref "R10") (pin "2") (pinfunction "2_2") (pintype "passive"))
      (node (ref "U3") (pin "20") (pinfunction "VREF+_20") (pintype "passive"))
    )
    (net (code "179") (name "unconnected-(J0-PadMP1)") (class "Default")
      (node (ref "J0") (pin "MP1") (pinfunction "MP1_MP1") (pintype "passive+no_connect"))
    )
    (net (code "180") (name "unconnected-(J0-PadMP2)") (class "Default")
      (node (ref "J0") (pin "MP2") (pinfunction "MP2_MP2") (pintype "passive+no_connect"))
    )
    (net (code "181") (name "unconnected-(SD1-CD-Pad9)") (class "Default")
      (node (ref "SD1") (pin "9") (pinfunction "CD_9") (pintype "passive+no_connect"))
    )
    (net (code "182") (name "unconnected-(U5-RESV-Pad7)") (class "Default")
      (node (ref "U5") (pin "7") (pinfunction "RESV_7") (pintype "passive+no_connect"))
    )
    (net (code "183") (name "unconnected-(U8-INT1-Pad16)") (class "Default")
      (node (ref "U8") (pin "16") (pinfunction "INT1_16") (pintype "bidirectional"))
    )
    (net (code "184") (name "unconnected-(U8-INT2-Pad1)") (class "Default")
      (node (ref "U8") (pin "1") (pinfunction "INT2_1") (pintype "bidirectional"))
    )
    (net (code "185") (name "unconnected-(U8-INT3-Pad12)") (class "Default")
      (node (ref "U8") (pin "12") (pinfunction "INT3_12") (pintype "output"))
    )
    (net (code "186") (name "unconnected-(U8-INT4-Pad13)") (class "Default")
      (node (ref "U8") (pin "13") (pinfunction "INT4_13") (pintype "output"))
    )
    (net (code "187") (name "unconnected-(U11-RSV-PadA4)") (class "Default")
      (node (ref "U11") (pin "A4") (pinfunction "RSV_A4") (pintype "passive+no_connect"))
    )
    (net (code "188") (name "unconnected-(U11-TST1-PadA1)") (class "Default")
      (node (ref "U11") (pin "A1") (pinfunction "TST1_A1") (pintype "passive+no_connect"))
    )
    (net (code "189") (name "unconnected-(U11-TST2-PadC2)") (class "Default")
      (node (ref "U11") (pin "C2") (pinfunction "TST2_C2") (pintype "passive+no_connect"))
    )
    (net (code "190") (name "unconnected-(U11-TST6-PadB3)") (class "Default")
      (node (ref "U11") (pin "B3") (pinfunction "TST6_B3") (pintype "passive+no_connect"))
    )
    (net (code "191") (name "unconnected-(U13-NC-Pad3)") (class "Default")
      (node (ref "U13") (pin "3") (pinfunction "NC_3") (pintype "passive+no_connect"))
    )
    (net (code "192") (name "unconnected-(U13-NC-Pad5)") (class "Default")
      (node (ref "U13") (pin "5") (pinfunction "NC_5") (pintype "passive+no_connect"))
    )
    (net (code "193") (name "unconnected-(U13-NC-Pad6)") (class "Default")
      (node (ref "U13") (pin "6") (pinfunction "NC_6") (pintype "passive+no_connect"))
    )
    (net (code "194") (name "unconnected-(U13-NC-Pad7)") (class "Default")
      (node (ref "U13") (pin "7") (pinfunction "NC_7") (pintype "passive+no_connect"))
    )
    (net (code "195") (name "unconnected-(U13-NC-Pad14)") (class "Default")
      (node (ref "U13") (pin "14") (pinfunction "NC_14") (pintype "passive+no_connect"))
    )
    (net (code "196") (name "unconnected-(U15-N{slash}C-PadB3)") (class "Default")
      (node (ref "U15") (pin "B3") (pinfunction "N/C_B3") (pintype "passive+no_connect"))
    )
    (net (code "197") (name "unconnected-(U15-N{slash}C-PadC2)") (class "Default")
      (node (ref "U15") (pin "C2") (pinfunction "N/C_C2") (pintype "passive+no_connect"))
    )
    (net (code "198") (name "unconnected-(U15-N{slash}C-PadC3)") (class "Default")
      (node (ref "U15") (pin "C3") (pinfunction "N/C_C3") (pintype "passive+no_connect"))
    )
    (net (code "199") (name "unconnected-(U16-ENA-Pad5)") (class "Default")
      (node (ref "U16") (pin "5") (pinfunction "ENA_5") (pintype "passive+no_connect"))
    )
    (net (code "200") (name "unconnected-(U16-NC-Pad2)") (class "Default")
      (node (ref "U16") (pin "2") (pinfunction "NC_2") (pintype "passive+no_connect"))
    )
    (net (code "201") (name "unconnected-(U16-NC-Pad3)") (class "Default")
      (node (ref "U16") (pin "3") (pinfunction "NC_3") (pintype "passive+no_connect"))
    )
    (net (code "202") (name "unconnected-(USB0-CC1-Pad4)") (class "Default")
      (node (ref "USB0") (pin "4") (pinfunction "CC1_4") (pintype "passive+no_connect"))
    )
    (net (code "203") (name "unconnected-(USB0-CC2-Pad10)") (class "Default")
      (node (ref "USB0") (pin "10") (pinfunction "CC2_10") (pintype "passive+no_connect"))
    )
    (net (code "204") (name "unconnected-(USB0-SBU1-Pad9)") (class "Default")
      (node (ref "USB0") (pin "9") (pinfunction "SBU1_9") (pintype "passive+no_connect"))
    )
    (net (code "205") (name "unconnected-(USB0-SBU2-Pad3)") (class "Default")
      (node (ref "USB0") (pin "3") (pinfunction "SBU2_3") (pintype "passive+no_connect"))
    )
  )
)
